# ECU-V1_3.net
KiCad netlist of a schematic drawn in EAGLE
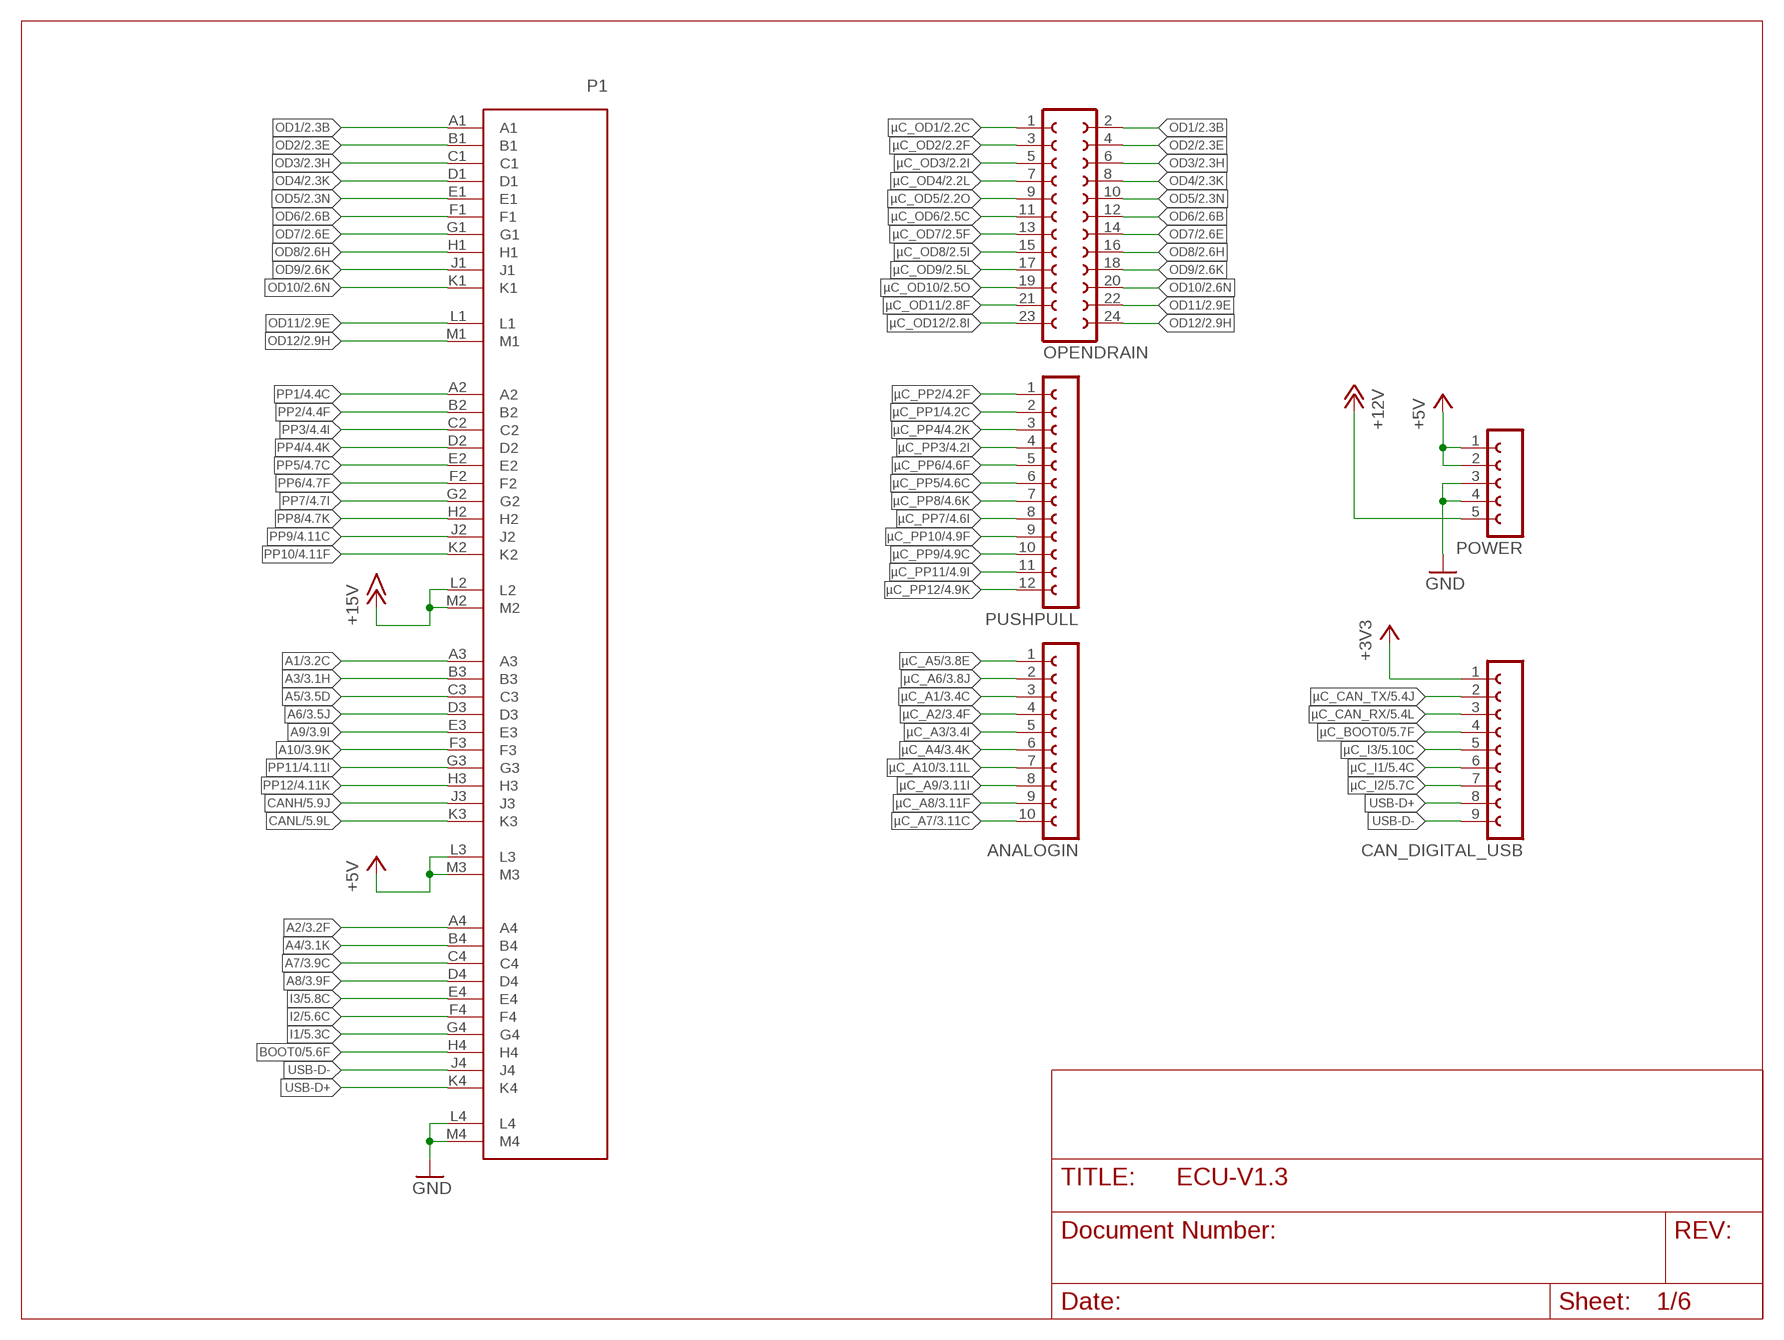
[diagram p0: schematic, sheet 1]
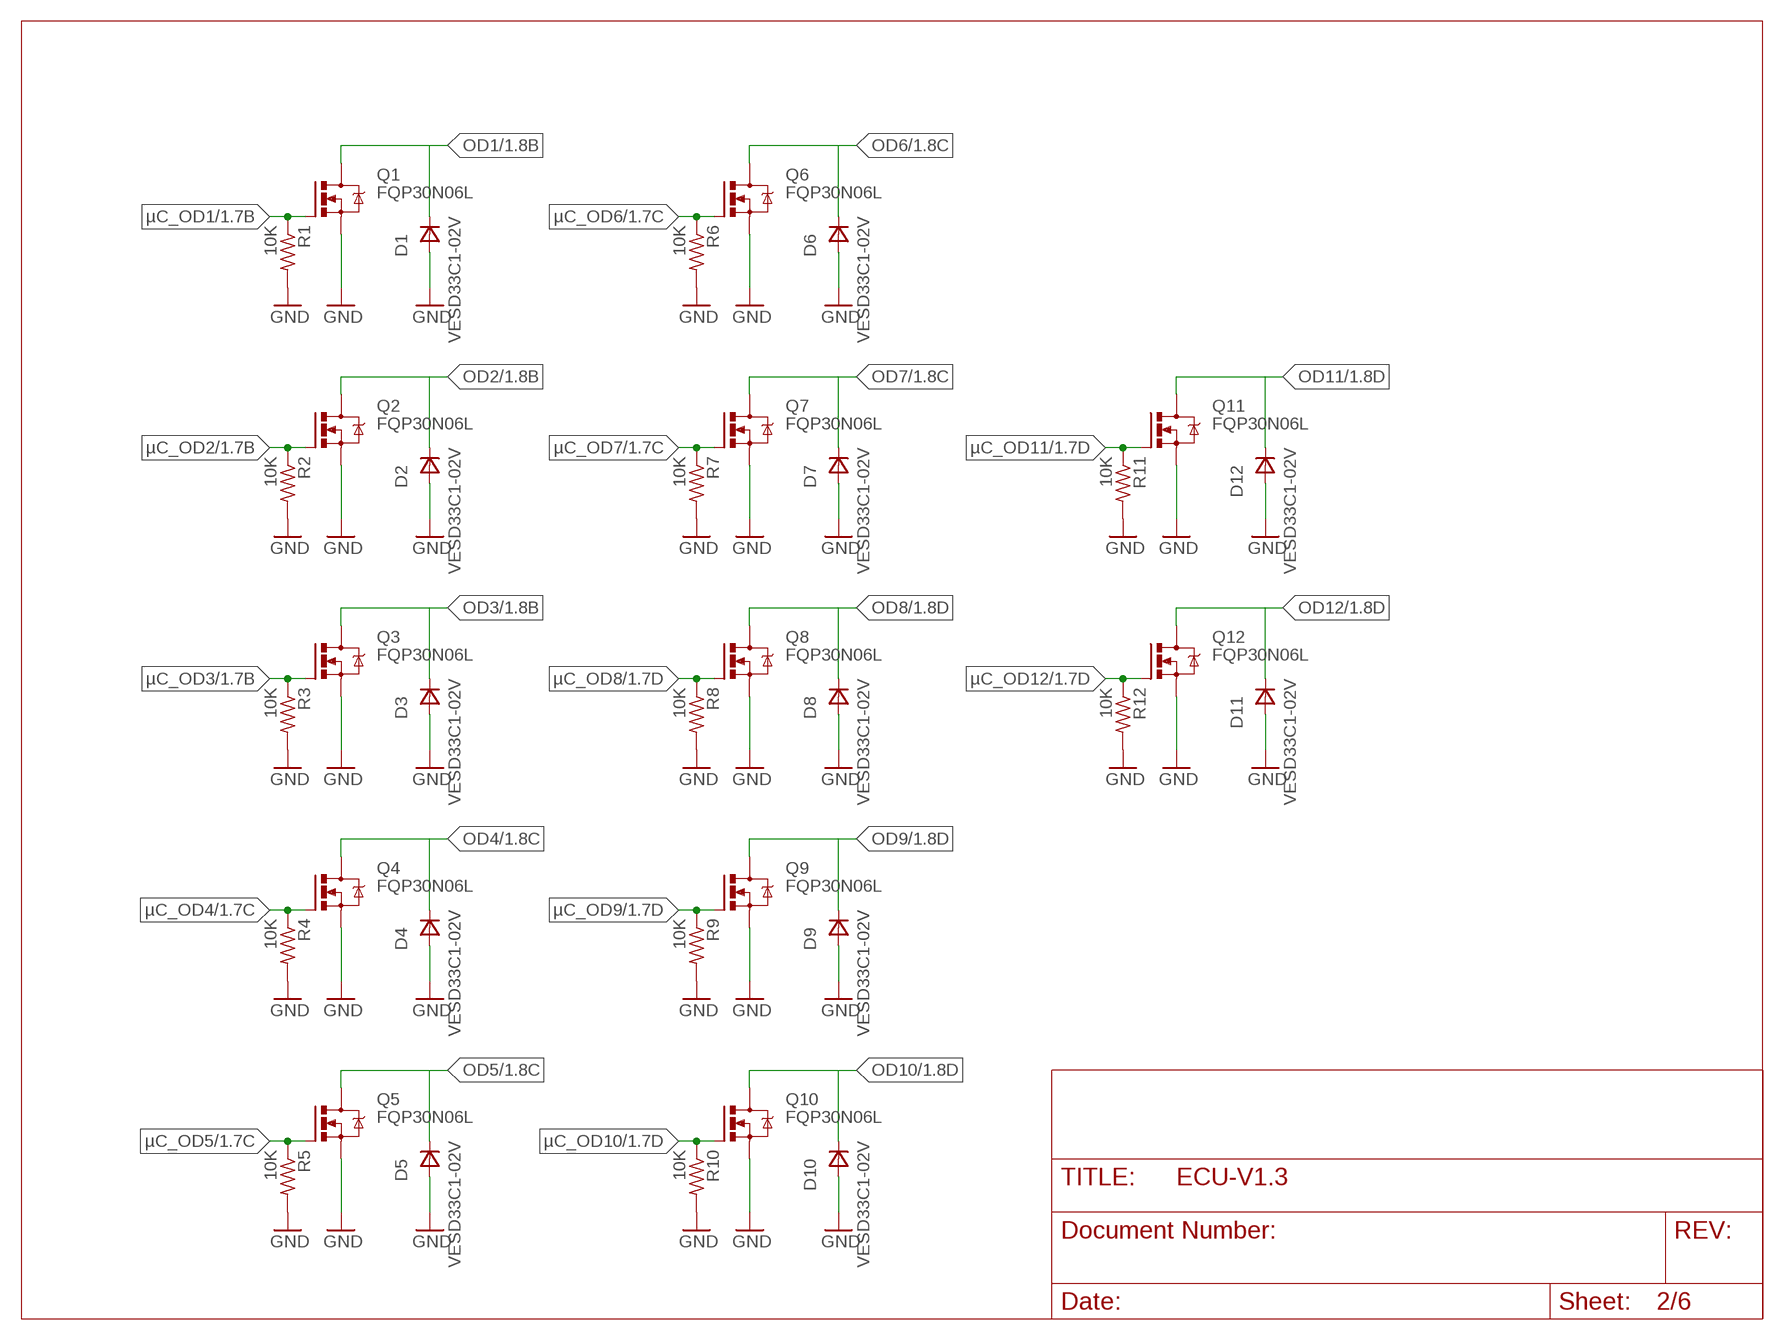
[diagram p1: schematic, sheet 2]
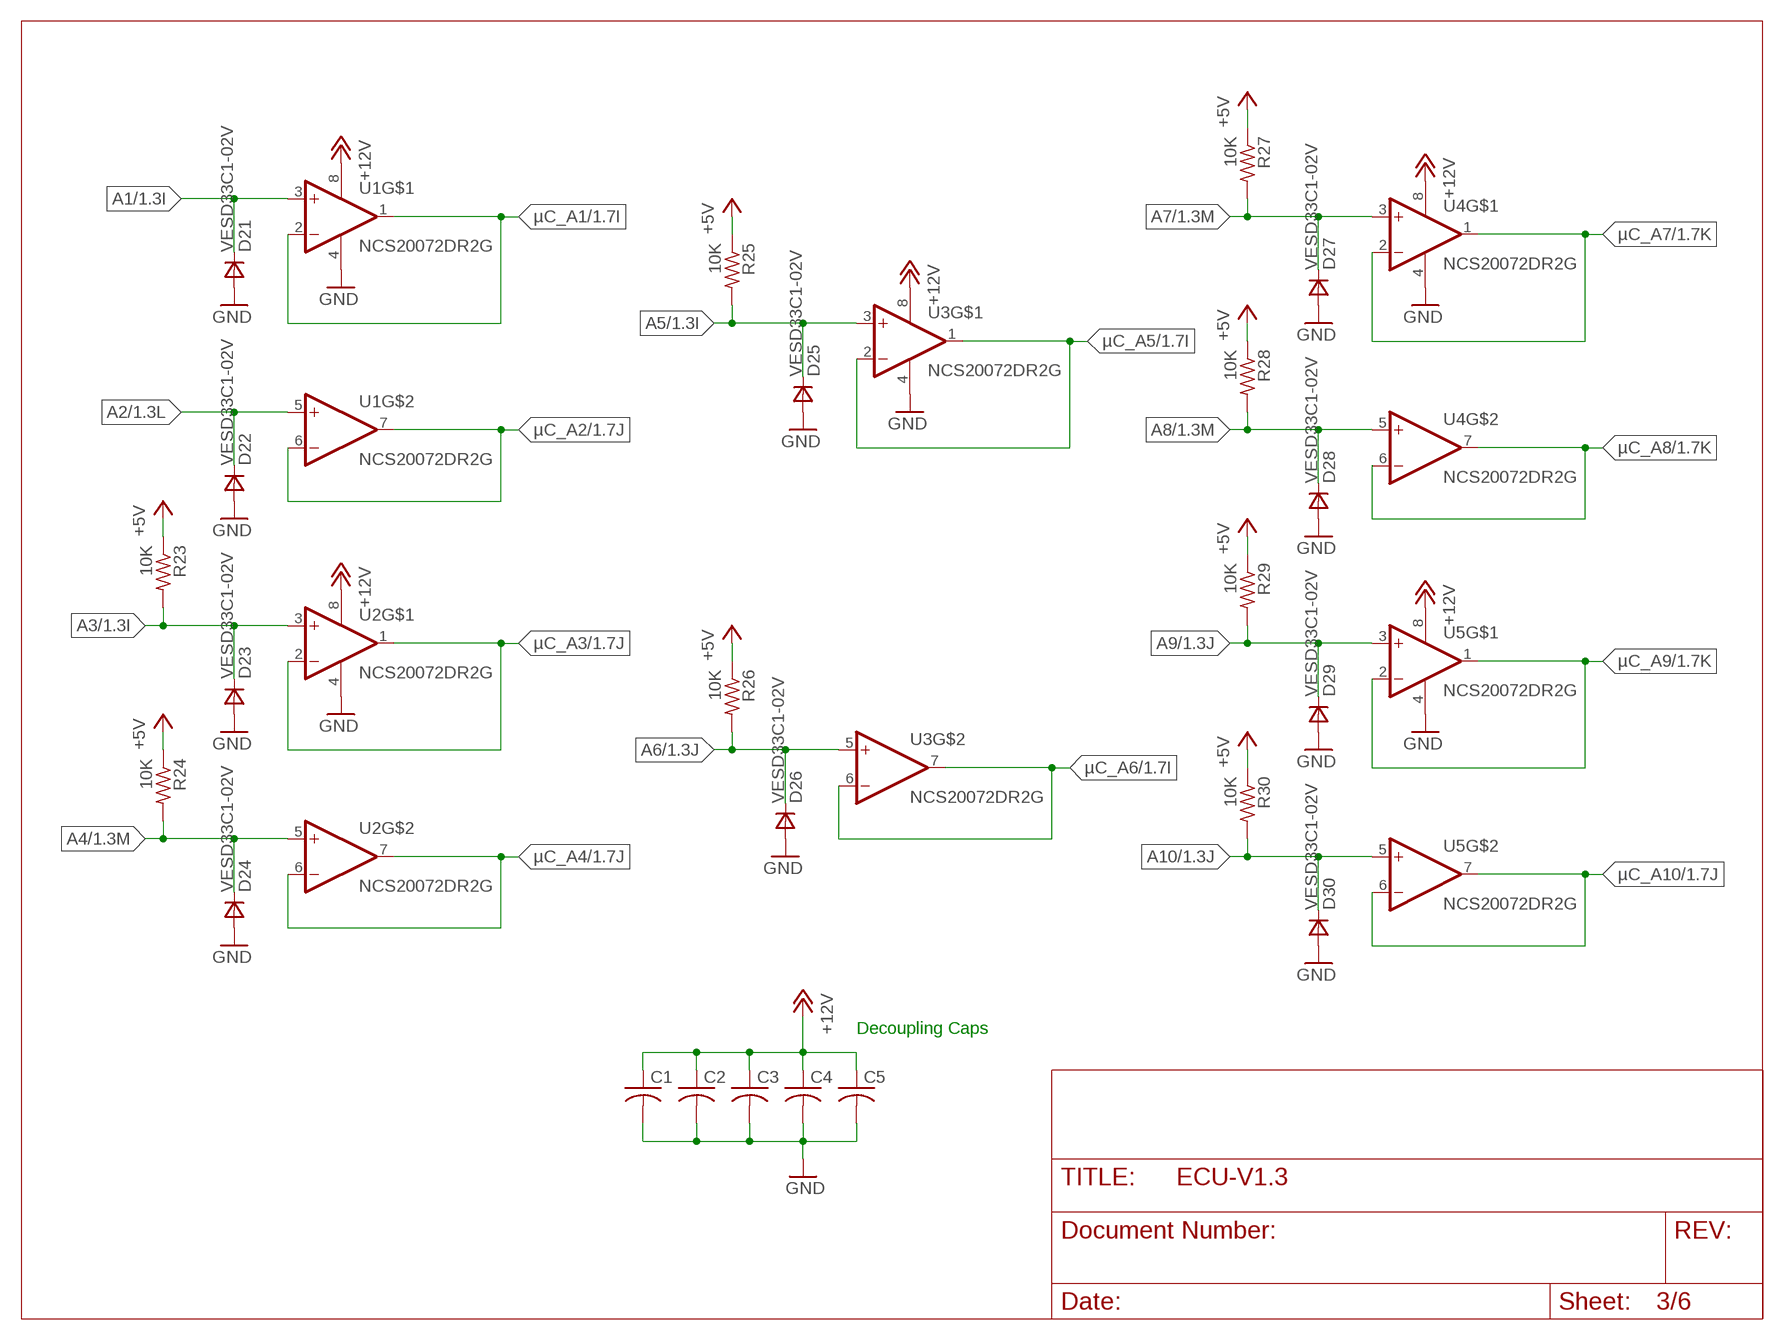
[diagram p2: schematic, sheet 3]
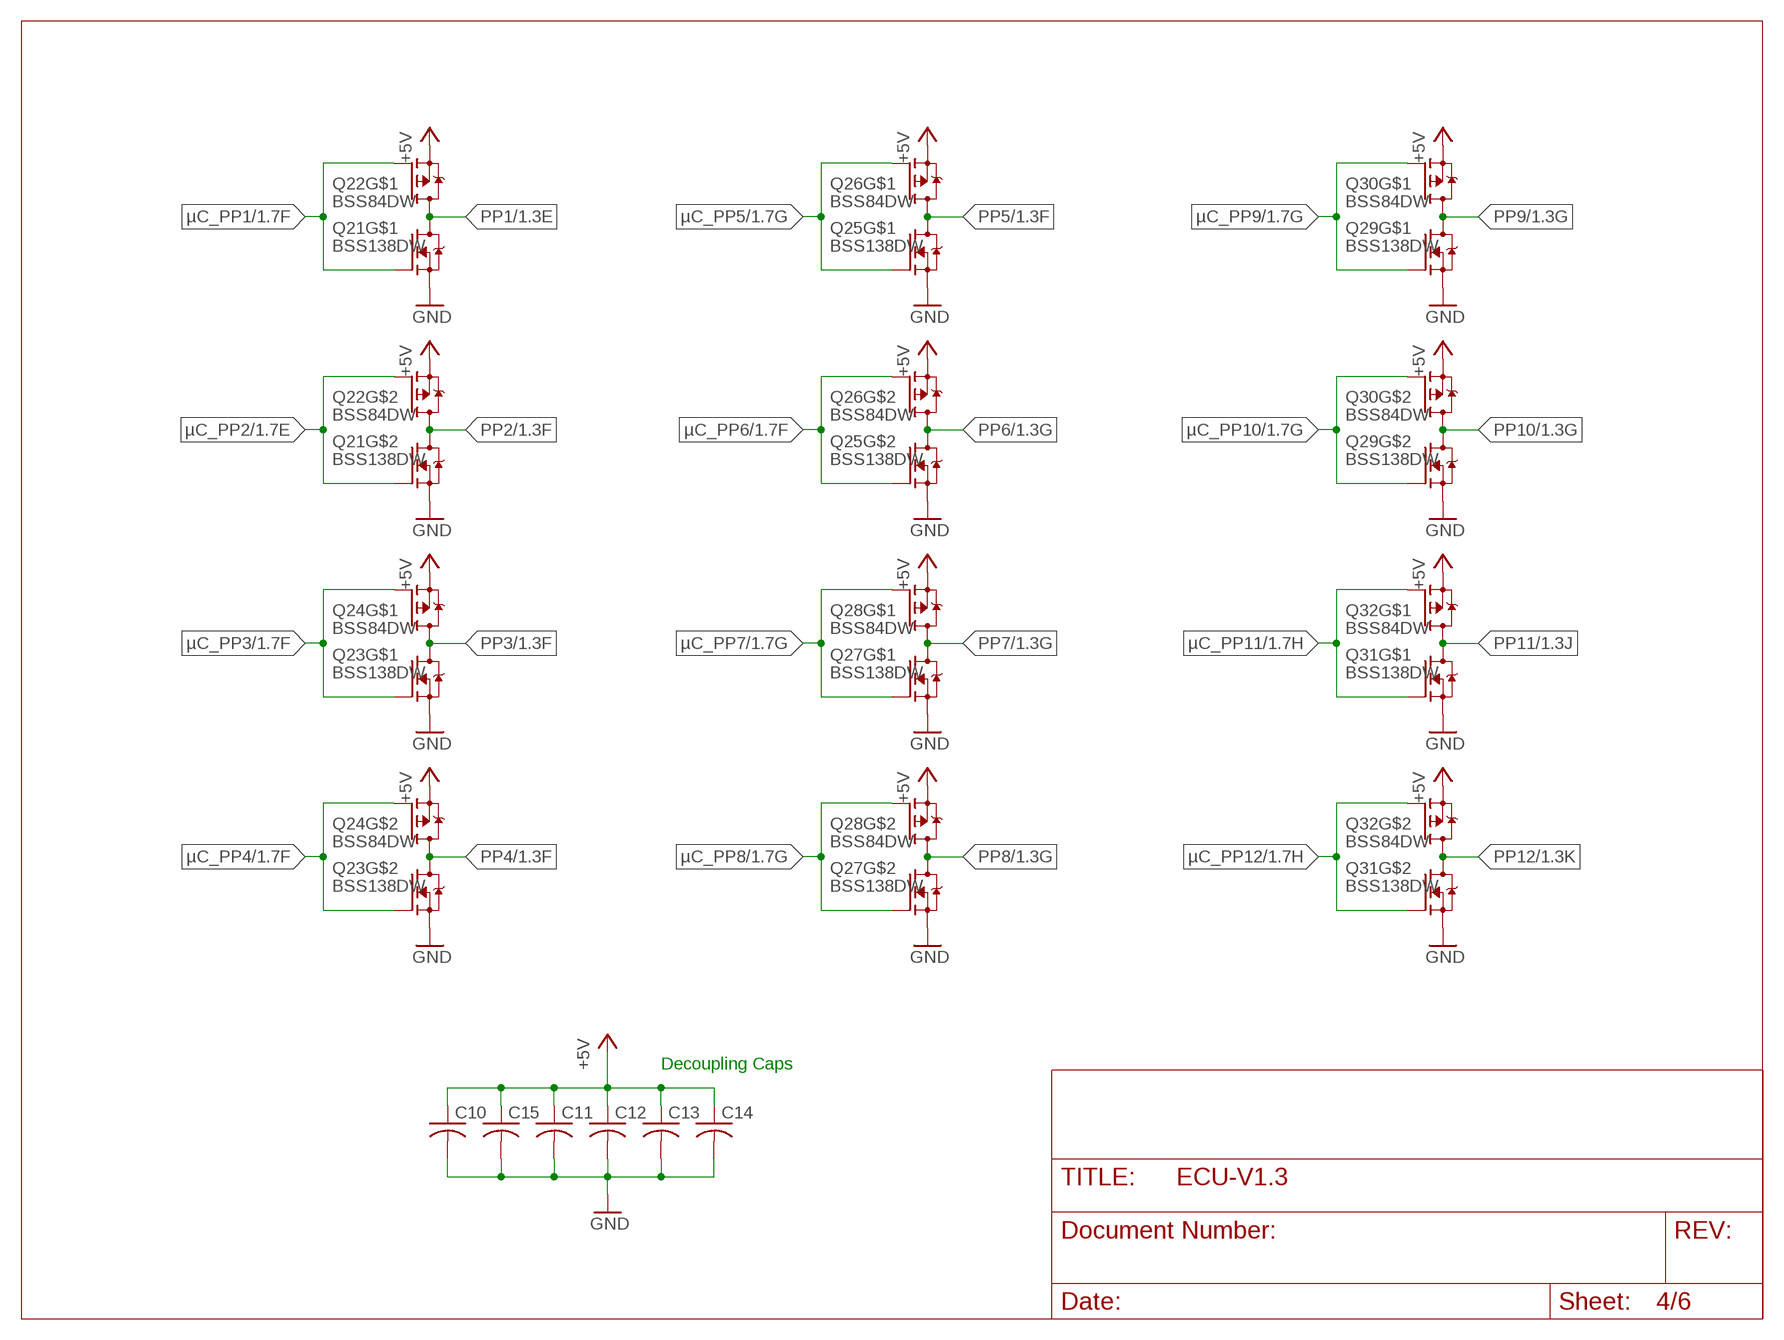
[diagram p3: schematic, sheet 4]
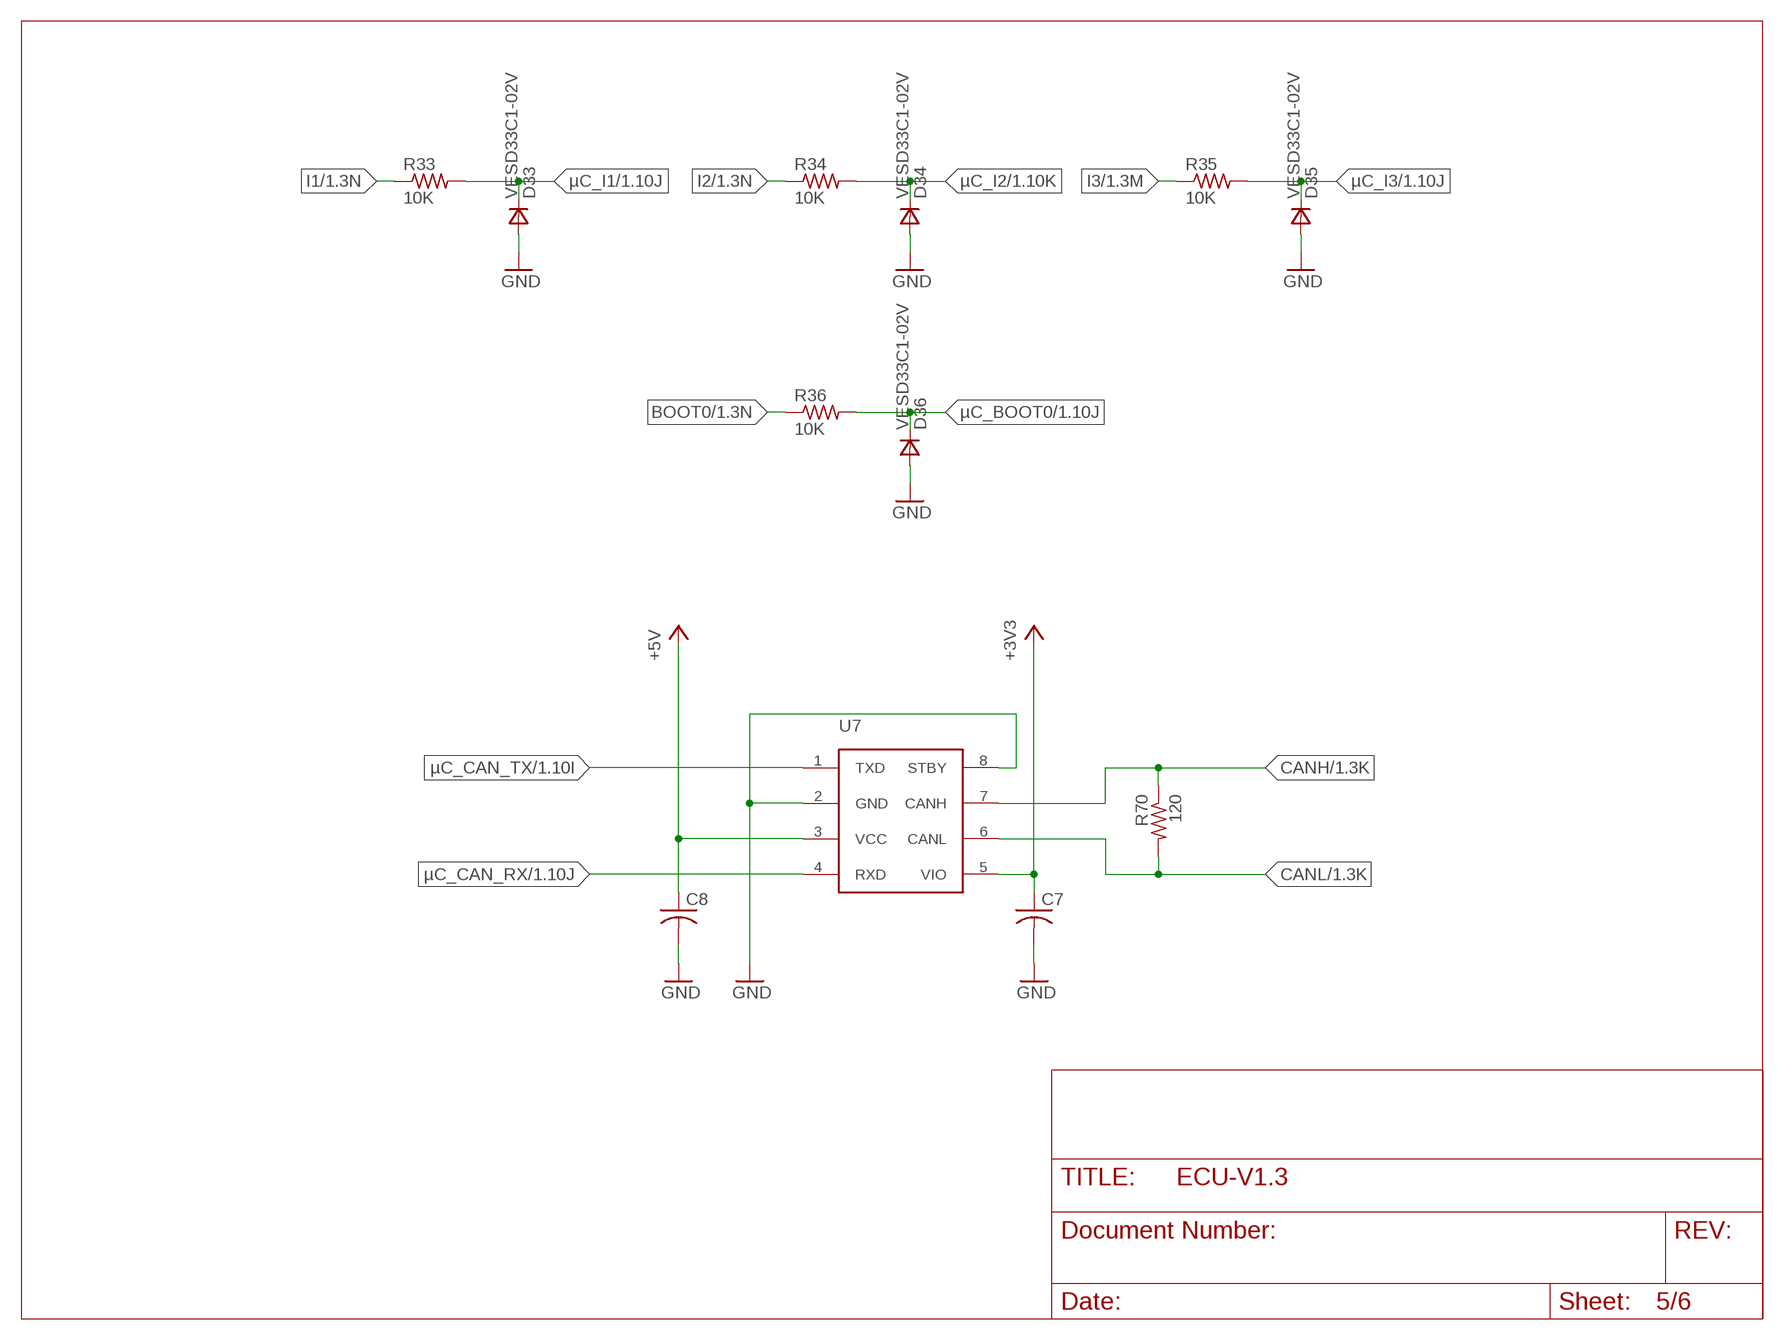
[diagram p4: schematic, sheet 5]
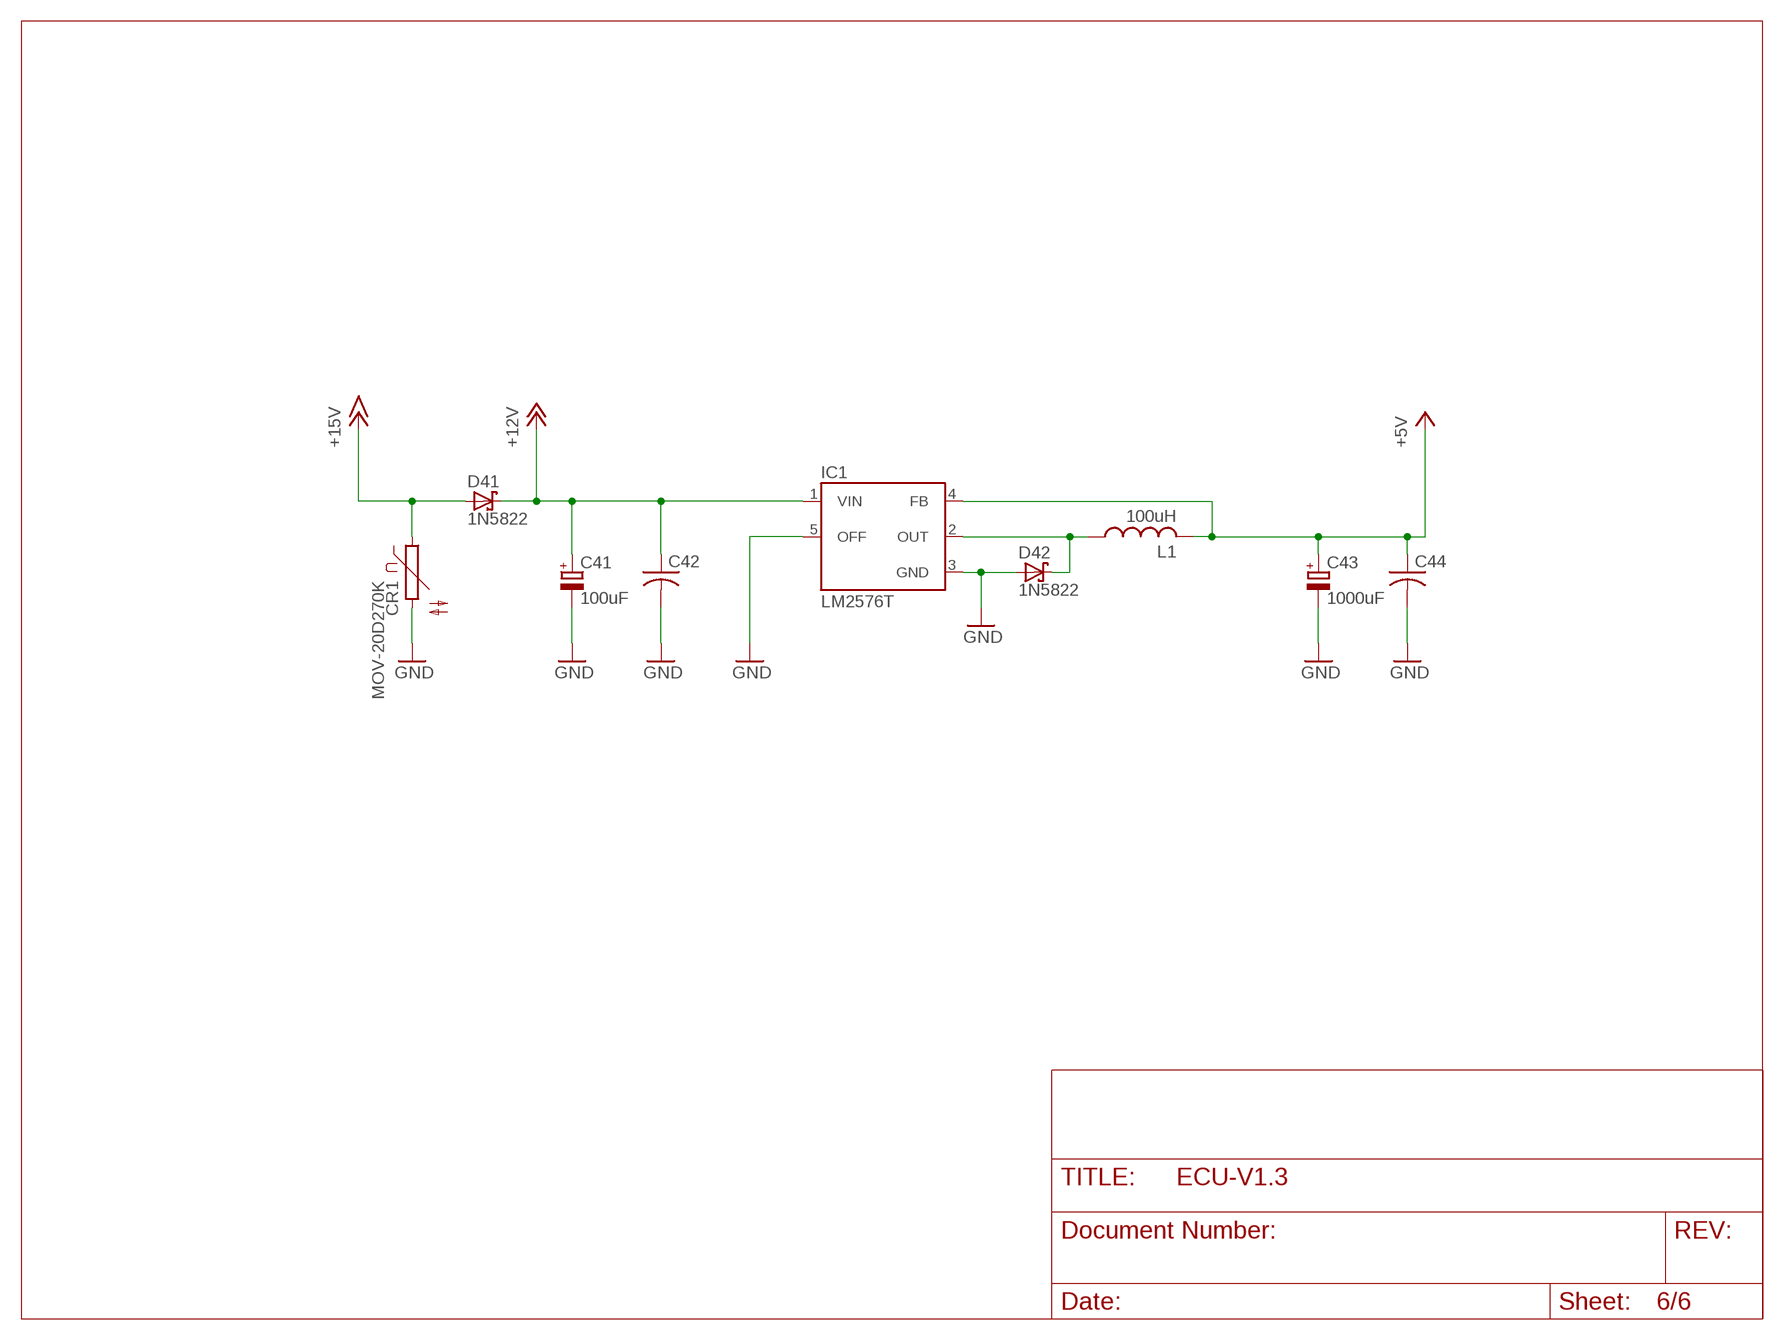
[diagram p5: schematic, sheet 6]

(export (version "E")
  (design (tool "Eeschema 10.0.6"))
  (components
    (comp (ref "C41")
      (value "100uF")
      (footprint "eagle-import:E3,5-10")
      (libsource (lib "eagle-import") (part "CPOL-EUE3.5-10"))
    )
    (comp (ref "C42")
      (value "C-USC0805")
      (footprint "eagle-import:C0805")
      (libsource (lib "eagle-import") (part "C-USC0805"))
    )
    (comp (ref "C43")
      (value "1000uF")
      (footprint "eagle-import:E3,5-10")
      (libsource (lib "eagle-import") (part "CPOL-EUE3.5-10"))
    )
    (comp (ref "C44")
      (value "C-USC0805")
      (footprint "eagle-import:C0805")
      (libsource (lib "eagle-import") (part "C-USC0805"))
    )
    (comp (ref "CR1")
      (value "MOV-20D270K")
      (footprint "eagle-import:S14K40")
      (libsource (lib "eagle-import") (part "S14K40"))
    )
    (comp (ref "D41")
      (value "1N5822")
      (footprint "eagle-import:DIODE_DO35-7")
      (libsource (lib "eagle-import") (part "SCHOTTKY-DIODEDO35-7"))
    )
    (comp (ref "D42")
      (value "1N5822")
      (footprint "eagle-import:DIODE_DO35-7")
      (libsource (lib "eagle-import") (part "SCHOTTKY-DIODEDO35-7"))
    )
    (comp (ref "IC1")
      (value "LM2576T")
      (footprint "eagle-import:TO220-5")
      (libsource (lib "eagle-import") (part "LM2576T"))
    )
    (comp (ref "L1")
      (value "100uH")
      (footprint "eagle-import:6000-XXXX-RC")
      (libsource (lib "eagle-import") (part "L-US6000-XXX-RC"))
    )
    (comp (ref "C1")
      (value "C-USC0805")
      (footprint "eagle-import:C0805")
      (libsource (lib "eagle-import") (part "C-USC0805"))
    )
    (comp (ref "C2")
      (value "C-USC0805")
      (footprint "eagle-import:C0805")
      (libsource (lib "eagle-import") (part "C-USC0805"))
    )
    (comp (ref "C3")
      (value "C-USC0805")
      (footprint "eagle-import:C0805")
      (libsource (lib "eagle-import") (part "C-USC0805"))
    )
    (comp (ref "C4")
      (value "C-USC0805")
      (footprint "eagle-import:C0805")
      (libsource (lib "eagle-import") (part "C-USC0805"))
    )
    (comp (ref "C5")
      (value "C-USC0805")
      (footprint "eagle-import:C0805")
      (libsource (lib "eagle-import") (part "C-USC0805"))
    )
    (comp (ref "D21")
      (value "VESD33C1-02V")
      (footprint "eagle-import:SOD323")
      (fields (field (name "MPN") "CDSOD323-T05C"))
      (libsource (lib "eagle-import") (part "DSOD323"))
    )
    (comp (ref "D22")
      (value "VESD33C1-02V")
      (footprint "eagle-import:SOD323")
      (fields (field (name "MPN") "CDSOD323-T05C"))
      (libsource (lib "eagle-import") (part "DSOD323"))
    )
    (comp (ref "D23")
      (value "VESD33C1-02V")
      (footprint "eagle-import:SOD323")
      (fields (field (name "MPN") "CDSOD323-T05C"))
      (libsource (lib "eagle-import") (part "DSOD323"))
    )
    (comp (ref "D24")
      (value "VESD33C1-02V")
      (footprint "eagle-import:SOD323")
      (fields (field (name "MPN") "CDSOD323-T05C"))
      (libsource (lib "eagle-import") (part "DSOD323"))
    )
    (comp (ref "D25")
      (value "VESD33C1-02V")
      (footprint "eagle-import:SOD323")
      (fields (field (name "MPN") "CDSOD323-T05C"))
      (libsource (lib "eagle-import") (part "DSOD323"))
    )
    (comp (ref "D26")
      (value "VESD33C1-02V")
      (footprint "eagle-import:SOD323")
      (fields (field (name "MPN") "CDSOD323-T05C"))
      (libsource (lib "eagle-import") (part "DSOD323"))
    )
    (comp (ref "D27")
      (value "VESD33C1-02V")
      (footprint "eagle-import:SOD323")
      (fields (field (name "MPN") "CDSOD323-T05C"))
      (libsource (lib "eagle-import") (part "DSOD323"))
    )
    (comp (ref "D28")
      (value "VESD33C1-02V")
      (footprint "eagle-import:SOD323")
      (fields (field (name "MPN") "CDSOD323-T05C"))
      (libsource (lib "eagle-import") (part "DSOD323"))
    )
    (comp (ref "D29")
      (value "VESD33C1-02V")
      (footprint "eagle-import:SOD323")
      (fields (field (name "MPN") "CDSOD323-T05C"))
      (libsource (lib "eagle-import") (part "DSOD323"))
    )
    (comp (ref "D30")
      (value "VESD33C1-02V")
      (footprint "eagle-import:SOD323")
      (fields (field (name "MPN") "CDSOD323-T05C"))
      (libsource (lib "eagle-import") (part "DSOD323"))
    )
    (comp (ref "R23")
      (value "10K")
      (footprint "eagle-import:R0805")
      (libsource (lib "eagle-import") (part "R-US_R0805"))
    )
    (comp (ref "R24")
      (value "10K")
      (footprint "eagle-import:R0805")
      (libsource (lib "eagle-import") (part "R-US_R0805"))
    )
    (comp (ref "R25")
      (value "10K")
      (footprint "eagle-import:R0805")
      (libsource (lib "eagle-import") (part "R-US_R0805"))
    )
    (comp (ref "R26")
      (value "10K")
      (footprint "eagle-import:R0805")
      (libsource (lib "eagle-import") (part "R-US_R0805"))
    )
    (comp (ref "R27")
      (value "10K")
      (footprint "eagle-import:R0805")
      (libsource (lib "eagle-import") (part "R-US_R0805"))
    )
    (comp (ref "R28")
      (value "10K")
      (footprint "eagle-import:R0805")
      (libsource (lib "eagle-import") (part "R-US_R0805"))
    )
    (comp (ref "R29")
      (value "10K")
      (footprint "eagle-import:R0805")
      (libsource (lib "eagle-import") (part "R-US_R0805"))
    )
    (comp (ref "R30")
      (value "10K")
      (footprint "eagle-import:R0805")
      (libsource (lib "eagle-import") (part "R-US_R0805"))
    )
    (comp (ref "U1")
      (value "NCS20072DR2G")
      (footprint "eagle-import:SOIC8")
      (libsource (lib "eagle-import") (part "NCS20072DR2G"))
    )
    (comp (ref "U2")
      (value "NCS20072DR2G")
      (footprint "eagle-import:SOIC8")
      (libsource (lib "eagle-import") (part "NCS20072DR2G"))
    )
    (comp (ref "U3")
      (value "NCS20072DR2G")
      (footprint "eagle-import:SOIC8")
      (libsource (lib "eagle-import") (part "NCS20072DR2G"))
    )
    (comp (ref "U4")
      (value "NCS20072DR2G")
      (footprint "eagle-import:SOIC8")
      (libsource (lib "eagle-import") (part "NCS20072DR2G"))
    )
    (comp (ref "U5")
      (value "NCS20072DR2G")
      (footprint "eagle-import:SOIC8")
      (libsource (lib "eagle-import") (part "NCS20072DR2G"))
    )
    (comp (ref "D1")
      (value "VESD33C1-02V")
      (footprint "eagle-import:SOD323")
      (fields (field (name "MPN") "CDSOD323-T05C"))
      (libsource (lib "eagle-import") (part "DSOD323"))
    )
    (comp (ref "D2")
      (value "VESD33C1-02V")
      (footprint "eagle-import:SOD323")
      (fields (field (name "MPN") "CDSOD323-T05C"))
      (libsource (lib "eagle-import") (part "DSOD323"))
    )
    (comp (ref "D3")
      (value "VESD33C1-02V")
      (footprint "eagle-import:SOD323")
      (fields (field (name "MPN") "CDSOD323-T05C"))
      (libsource (lib "eagle-import") (part "DSOD323"))
    )
    (comp (ref "D4")
      (value "VESD33C1-02V")
      (footprint "eagle-import:SOD323")
      (fields (field (name "MPN") "CDSOD323-T05C"))
      (libsource (lib "eagle-import") (part "DSOD323"))
    )
    (comp (ref "D5")
      (value "VESD33C1-02V")
      (footprint "eagle-import:SOD323")
      (fields (field (name "MPN") "CDSOD323-T05C"))
      (libsource (lib "eagle-import") (part "DSOD323"))
    )
    (comp (ref "D6")
      (value "VESD33C1-02V")
      (footprint "eagle-import:SOD323")
      (fields (field (name "MPN") "CDSOD323-T05C"))
      (libsource (lib "eagle-import") (part "DSOD323"))
    )
    (comp (ref "D7")
      (value "VESD33C1-02V")
      (footprint "eagle-import:SOD323")
      (fields (field (name "MPN") "CDSOD323-T05C"))
      (libsource (lib "eagle-import") (part "DSOD323"))
    )
    (comp (ref "D8")
      (value "VESD33C1-02V")
      (footprint "eagle-import:SOD323")
      (fields (field (name "MPN") "CDSOD323-T05C"))
      (libsource (lib "eagle-import") (part "DSOD323"))
    )
    (comp (ref "D9")
      (value "VESD33C1-02V")
      (footprint "eagle-import:SOD323")
      (fields (field (name "MPN") "CDSOD323-T05C"))
      (libsource (lib "eagle-import") (part "DSOD323"))
    )
    (comp (ref "D10")
      (value "VESD33C1-02V")
      (footprint "eagle-import:SOD323")
      (fields (field (name "MPN") "CDSOD323-T05C"))
      (libsource (lib "eagle-import") (part "DSOD323"))
    )
    (comp (ref "D11")
      (value "VESD33C1-02V")
      (footprint "eagle-import:SOD323")
      (fields (field (name "MPN") "CDSOD323-T05C"))
      (libsource (lib "eagle-import") (part "DSOD323"))
    )
    (comp (ref "D12")
      (value "VESD33C1-02V")
      (footprint "eagle-import:SOD323")
      (fields (field (name "MPN") "CDSOD323-T05C"))
      (libsource (lib "eagle-import") (part "DSOD323"))
    )
    (comp (ref "Q1")
      (value "FQP30N06L")
      (footprint "eagle-import:TO220BV")
      (libsource (lib "eagle-import") (part "FQP30N06L"))
    )
    (comp (ref "Q2")
      (value "FQP30N06L")
      (footprint "eagle-import:TO220BV")
      (libsource (lib "eagle-import") (part "FQP30N06L"))
    )
    (comp (ref "Q3")
      (value "FQP30N06L")
      (footprint "eagle-import:TO220BV")
      (libsource (lib "eagle-import") (part "FQP30N06L"))
    )
    (comp (ref "Q4")
      (value "FQP30N06L")
      (footprint "eagle-import:TO220BV")
      (libsource (lib "eagle-import") (part "FQP30N06L"))
    )
    (comp (ref "Q5")
      (value "FQP30N06L")
      (footprint "eagle-import:TO220BV")
      (libsource (lib "eagle-import") (part "FQP30N06L"))
    )
    (comp (ref "Q6")
      (value "FQP30N06L")
      (footprint "eagle-import:TO220BV")
      (libsource (lib "eagle-import") (part "FQP30N06L"))
    )
    (comp (ref "Q7")
      (value "FQP30N06L")
      (footprint "eagle-import:TO220BV")
      (libsource (lib "eagle-import") (part "FQP30N06L"))
    )
    (comp (ref "Q8")
      (value "FQP30N06L")
      (footprint "eagle-import:TO220BV")
      (libsource (lib "eagle-import") (part "FQP30N06L"))
    )
    (comp (ref "Q9")
      (value "FQP30N06L")
      (footprint "eagle-import:TO220BV")
      (libsource (lib "eagle-import") (part "FQP30N06L"))
    )
    (comp (ref "Q10")
      (value "FQP30N06L")
      (footprint "eagle-import:TO220BV")
      (libsource (lib "eagle-import") (part "FQP30N06L"))
    )
    (comp (ref "Q11")
      (value "FQP30N06L")
      (footprint "eagle-import:TO220BV")
      (libsource (lib "eagle-import") (part "FQP30N06L"))
    )
    (comp (ref "Q12")
      (value "FQP30N06L")
      (footprint "eagle-import:TO220BV")
      (libsource (lib "eagle-import") (part "FQP30N06L"))
    )
    (comp (ref "R1")
      (value "10K")
      (footprint "eagle-import:R0805")
      (libsource (lib "eagle-import") (part "R-US_R0805"))
    )
    (comp (ref "R2")
      (value "10K")
      (footprint "eagle-import:R0805")
      (libsource (lib "eagle-import") (part "R-US_R0805"))
    )
    (comp (ref "R3")
      (value "10K")
      (footprint "eagle-import:R0805")
      (libsource (lib "eagle-import") (part "R-US_R0805"))
    )
    (comp (ref "R4")
      (value "10K")
      (footprint "eagle-import:R0805")
      (libsource (lib "eagle-import") (part "R-US_R0805"))
    )
    (comp (ref "R5")
      (value "10K")
      (footprint "eagle-import:R0805")
      (libsource (lib "eagle-import") (part "R-US_R0805"))
    )
    (comp (ref "R6")
      (value "10K")
      (footprint "eagle-import:R0805")
      (libsource (lib "eagle-import") (part "R-US_R0805"))
    )
    (comp (ref "R7")
      (value "10K")
      (footprint "eagle-import:R0805")
      (libsource (lib "eagle-import") (part "R-US_R0805"))
    )
    (comp (ref "R8")
      (value "10K")
      (footprint "eagle-import:R0805")
      (libsource (lib "eagle-import") (part "R-US_R0805"))
    )
    (comp (ref "R9")
      (value "10K")
      (footprint "eagle-import:R0805")
      (libsource (lib "eagle-import") (part "R-US_R0805"))
    )
    (comp (ref "R10")
      (value "10K")
      (footprint "eagle-import:R0805")
      (libsource (lib "eagle-import") (part "R-US_R0805"))
    )
    (comp (ref "R11")
      (value "10K")
      (footprint "eagle-import:R0805")
      (libsource (lib "eagle-import") (part "R-US_R0805"))
    )
    (comp (ref "R12")
      (value "10K")
      (footprint "eagle-import:R0805")
      (libsource (lib "eagle-import") (part "R-US_R0805"))
    )
    (comp (ref "ANALOGIN")
      (value "FE10-1")
      (footprint "eagle-import:FE10")
      (libsource (lib "eagle-import") (part "FE10-1"))
    )
    (comp (ref "CAN_DIGITAL_USB")
      (value "FE09-1")
      (footprint "eagle-import:FE09")
      (libsource (lib "eagle-import") (part "FE09-1"))
    )
    (comp (ref "OPENDRAIN")
      (value "FE12-2")
      (footprint "eagle-import:FE12-2")
      (libsource (lib "eagle-import") (part "FE12-2"))
    )
    (comp (ref "P1")
      (value "ECU-CONNECTOR")
      (footprint "eagle-import:ECU-CONNECTOR")
      (libsource (lib "eagle-import") (part "ECU-CONNECTOR"))
    )
    (comp (ref "POWER")
      (value "FE05-1")
      (footprint "eagle-import:FE05-1")
      (libsource (lib "eagle-import") (part "FE05-1"))
    )
    (comp (ref "PUSHPULL")
      (value "FE12-1")
      (footprint "eagle-import:FE12")
      (libsource (lib "eagle-import") (part "FE12-1"))
    )
    (comp (ref "C10")
      (value "C-USC0805")
      (footprint "eagle-import:C0805")
      (libsource (lib "eagle-import") (part "C-USC0805"))
    )
    (comp (ref "C11")
      (value "C-USC0805")
      (footprint "eagle-import:C0805")
      (libsource (lib "eagle-import") (part "C-USC0805"))
    )
    (comp (ref "C12")
      (value "C-USC0805")
      (footprint "eagle-import:C0805")
      (libsource (lib "eagle-import") (part "C-USC0805"))
    )
    (comp (ref "C13")
      (value "C-USC0805")
      (footprint "eagle-import:C0805")
      (libsource (lib "eagle-import") (part "C-USC0805"))
    )
    (comp (ref "C14")
      (value "C-USC0805")
      (footprint "eagle-import:C0805")
      (libsource (lib "eagle-import") (part "C-USC0805"))
    )
    (comp (ref "C15")
      (value "C-USC0805")
      (footprint "eagle-import:C0805")
      (libsource (lib "eagle-import") (part "C-USC0805"))
    )
    (comp (ref "Q21")
      (value "BSS138DW")
      (footprint "eagle-import:SOT363_INFINEON")
      (libsource (lib "eagle-import") (part "BSS138DW"))
    )
    (comp (ref "Q22")
      (value "BSS84DW")
      (footprint "eagle-import:SOT363_INFINEON")
      (libsource (lib "eagle-import") (part "BSS84DW"))
    )
    (comp (ref "Q23")
      (value "BSS138DW")
      (footprint "eagle-import:SOT363_INFINEON")
      (libsource (lib "eagle-import") (part "BSS138DW"))
    )
    (comp (ref "Q24")
      (value "BSS84DW")
      (footprint "eagle-import:SOT363_INFINEON")
      (libsource (lib "eagle-import") (part "BSS84DW"))
    )
    (comp (ref "Q25")
      (value "BSS138DW")
      (footprint "eagle-import:SOT363_INFINEON")
      (libsource (lib "eagle-import") (part "BSS138DW"))
    )
    (comp (ref "Q26")
      (value "BSS84DW")
      (footprint "eagle-import:SOT363_INFINEON")
      (libsource (lib "eagle-import") (part "BSS84DW"))
    )
    (comp (ref "Q27")
      (value "BSS138DW")
      (footprint "eagle-import:SOT363_INFINEON")
      (libsource (lib "eagle-import") (part "BSS138DW"))
    )
    (comp (ref "Q28")
      (value "BSS84DW")
      (footprint "eagle-import:SOT363_INFINEON")
      (libsource (lib "eagle-import") (part "BSS84DW"))
    )
    (comp (ref "Q29")
      (value "BSS138DW")
      (footprint "eagle-import:SOT363_INFINEON")
      (libsource (lib "eagle-import") (part "BSS138DW"))
    )
    (comp (ref "Q30")
      (value "BSS84DW")
      (footprint "eagle-import:SOT363_INFINEON")
      (libsource (lib "eagle-import") (part "BSS84DW"))
    )
    (comp (ref "Q31")
      (value "BSS138DW")
      (footprint "eagle-import:SOT363_INFINEON")
      (libsource (lib "eagle-import") (part "BSS138DW"))
    )
    (comp (ref "Q32")
      (value "BSS84DW")
      (footprint "eagle-import:SOT363_INFINEON")
      (libsource (lib "eagle-import") (part "BSS84DW"))
    )
    (comp (ref "C7")
      (value "C-USC0805")
      (footprint "eagle-import:C0805")
      (libsource (lib "eagle-import") (part "C-USC0805"))
    )
    (comp (ref "C8")
      (value "C-USC0805")
      (footprint "eagle-import:C0805")
      (libsource (lib "eagle-import") (part "C-USC0805"))
    )
    (comp (ref "D33")
      (value "VESD33C1-02V")
      (footprint "eagle-import:SOD323")
      (fields (field (name "MPN") "CDSOD323-T05C"))
      (libsource (lib "eagle-import") (part "DSOD323"))
    )
    (comp (ref "D34")
      (value "VESD33C1-02V")
      (footprint "eagle-import:SOD323")
      (fields (field (name "MPN") "CDSOD323-T05C"))
      (libsource (lib "eagle-import") (part "DSOD323"))
    )
    (comp (ref "D35")
      (value "VESD33C1-02V")
      (footprint "eagle-import:SOD323")
      (fields (field (name "MPN") "CDSOD323-T05C"))
      (libsource (lib "eagle-import") (part "DSOD323"))
    )
    (comp (ref "D36")
      (value "VESD33C1-02V")
      (footprint "eagle-import:SOD323")
      (fields (field (name "MPN") "CDSOD323-T05C"))
      (libsource (lib "eagle-import") (part "DSOD323"))
    )
    (comp (ref "R33")
      (value "10K")
      (footprint "eagle-import:R0805")
      (libsource (lib "eagle-import") (part "R-US_R0805"))
    )
    (comp (ref "R34")
      (value "10K")
      (footprint "eagle-import:R0805")
      (libsource (lib "eagle-import") (part "R-US_R0805"))
    )
    (comp (ref "R35")
      (value "10K")
      (footprint "eagle-import:R0805")
      (libsource (lib "eagle-import") (part "R-US_R0805"))
    )
    (comp (ref "R36")
      (value "10K")
      (footprint "eagle-import:R0805")
      (libsource (lib "eagle-import") (part "R-US_R0805"))
    )
    (comp (ref "R70")
      (value "120")
      (footprint "eagle-import:R0805")
      (libsource (lib "eagle-import") (part "R-US_R0805"))
    )
    (comp (ref "U7")
      (value "ATA6561-GA")
      (footprint "eagle-import:SO-08")
      (libsource (lib "eagle-import") (part "ATA6561-GA"))
    )
  )
  (nets
    (net (code "1") (name "+3V3") (class "Default")
      (node (ref "C7") (pin "1") (pinfunction "1_1") (pintype "passive"))
      (node (ref "CAN_DIGITAL_USB") (pin "1") (pinfunction "1_1") (pintype "passive"))
      (node (ref "U7") (pin "5") (pinfunction "VIO_5") (pintype "bidirectional"))
    )
    (net (code "2") (name "+5V") (class "Default")
      (node (ref "C10") (pin "1") (pinfunction "1_1") (pintype "passive"))
      (node (ref "C11") (pin "1") (pinfunction "1_1") (pintype "passive"))
      (node (ref "C12") (pin "1") (pinfunction "1_1") (pintype "passive"))
      (node (ref "C13") (pin "1") (pinfunction "1_1") (pintype "passive"))
      (node (ref "C14") (pin "1") (pinfunction "1_1") (pintype "passive"))
      (node (ref "C15") (pin "1") (pinfunction "1_1") (pintype "passive"))
      (node (ref "C43") (pin "+") (pinfunction "+_+") (pintype "passive"))
      (node (ref "C44") (pin "1") (pinfunction "1_1") (pintype "passive"))
      (node (ref "C8") (pin "1") (pinfunction "1_1") (pintype "passive"))
      (node (ref "IC1") (pin "4") (pinfunction "FB_4") (pintype "input"))
      (node (ref "L1") (pin "2") (pinfunction "2_2") (pintype "passive"))
      (node (ref "P1") (pin "L3") (pinfunction "L3_L3") (pintype "bidirectional"))
      (node (ref "P1") (pin "M3") (pinfunction "M3_M3") (pintype "bidirectional"))
      (node (ref "POWER") (pin "1") (pinfunction "1_1") (pintype "passive"))
      (node (ref "POWER") (pin "2") (pinfunction "2_2") (pintype "passive"))
      (node (ref "Q22") (pin "1") (pinfunction "S_1") (pintype "passive"))
      (node (ref "Q22") (pin "4") (pinfunction "S_4") (pintype "passive"))
      (node (ref "Q24") (pin "1") (pinfunction "S_1") (pintype "passive"))
      (node (ref "Q24") (pin "4") (pinfunction "S_4") (pintype "passive"))
      (node (ref "Q26") (pin "1") (pinfunction "S_1") (pintype "passive"))
      (node (ref "Q26") (pin "4") (pinfunction "S_4") (pintype "passive"))
      (node (ref "Q28") (pin "1") (pinfunction "S_1") (pintype "passive"))
      (node (ref "Q28") (pin "4") (pinfunction "S_4") (pintype "passive"))
      (node (ref "Q30") (pin "1") (pinfunction "S_1") (pintype "passive"))
      (node (ref "Q30") (pin "4") (pinfunction "S_4") (pintype "passive"))
      (node (ref "Q32") (pin "1") (pinfunction "S_1") (pintype "passive"))
      (node (ref "Q32") (pin "4") (pinfunction "S_4") (pintype "passive"))
      (node (ref "R23") (pin "1") (pinfunction "1_1") (pintype "passive"))
      (node (ref "R24") (pin "1") (pinfunction "1_1") (pintype "passive"))
      (node (ref "R25") (pin "1") (pinfunction "1_1") (pintype "passive"))
      (node (ref "R26") (pin "1") (pinfunction "1_1") (pintype "passive"))
      (node (ref "R27") (pin "1") (pinfunction "1_1") (pintype "passive"))
      (node (ref "R28") (pin "1") (pinfunction "1_1") (pintype "passive"))
      (node (ref "R29") (pin "1") (pinfunction "1_1") (pintype "passive"))
      (node (ref "R30") (pin "1") (pinfunction "1_1") (pintype "passive"))
      (node (ref "U7") (pin "3") (pinfunction "VCC_3") (pintype "bidirectional"))
    )
    (net (code "3") (name "+12V") (class "Default")
      (node (ref "C1") (pin "1") (pinfunction "1_1") (pintype "passive"))
      (node (ref "C2") (pin "1") (pinfunction "1_1") (pintype "passive"))
      (node (ref "C3") (pin "1") (pinfunction "1_1") (pintype "passive"))
      (node (ref "C4") (pin "1") (pinfunction "1_1") (pintype "passive"))
      (node (ref "C41") (pin "+") (pinfunction "+_+") (pintype "passive"))
      (node (ref "C42") (pin "1") (pinfunction "1_1") (pintype "passive"))
      (node (ref "C5") (pin "1") (pinfunction "1_1") (pintype "passive"))
      (node (ref "D41") (pin "C") (pinfunction "A_C") (pintype "passive"))
      (node (ref "IC1") (pin "1") (pinfunction "VIN_1") (pintype "power_in"))
      (node (ref "POWER") (pin "5") (pinfunction "5_5") (pintype "passive"))
      (node (ref "U1") (pin "8") (pinfunction "V+_8") (pintype "power_in"))
      (node (ref "U2") (pin "8") (pinfunction "V+_8") (pintype "power_in"))
      (node (ref "U3") (pin "8") (pinfunction "V+_8") (pintype "power_in"))
      (node (ref "U4") (pin "8") (pinfunction "V+_8") (pintype "power_in"))
      (node (ref "U5") (pin "8") (pinfunction "V+_8") (pintype "power_in"))
    )
    (net (code "4") (name "+15V") (class "Default")
      (node (ref "CR1") (pin "1") (pinfunction "1_1") (pintype "passive"))
      (node (ref "D41") (pin "A") (pinfunction "C_A") (pintype "passive"))
      (node (ref "P1") (pin "L2") (pinfunction "L2_L2") (pintype "bidirectional"))
      (node (ref "P1") (pin "M2") (pinfunction "M2_M2") (pintype "bidirectional"))
    )
    (net (code "5") (name "A1") (class "Default")
      (node (ref "D21") (pin "1") (pinfunction "C_1") (pintype "passive"))
      (node (ref "P1") (pin "A3") (pinfunction "A3_A3") (pintype "bidirectional"))
      (node (ref "U1") (pin "3") (pinfunction "+IN_3") (pintype "input"))
    )
    (net (code "6") (name "A2") (class "Default")
      (node (ref "D22") (pin "1") (pinfunction "C_1") (pintype "passive"))
      (node (ref "P1") (pin "A4") (pinfunction "A4_A4") (pintype "bidirectional"))
      (node (ref "U1") (pin "5") (pinfunction "+IN_5") (pintype "input"))
    )
    (net (code "7") (name "A3") (class "Default")
      (node (ref "D23") (pin "1") (pinfunction "C_1") (pintype "passive"))
      (node (ref "P1") (pin "B3") (pinfunction "B3_B3") (pintype "bidirectional"))
      (node (ref "R23") (pin "2") (pinfunction "2_2") (pintype "passive"))
      (node (ref "U2") (pin "3") (pinfunction "+IN_3") (pintype "input"))
    )
    (net (code "8") (name "A4") (class "Default")
      (node (ref "D24") (pin "1") (pinfunction "C_1") (pintype "passive"))
      (node (ref "P1") (pin "B4") (pinfunction "B4_B4") (pintype "bidirectional"))
      (node (ref "R24") (pin "2") (pinfunction "2_2") (pintype "passive"))
      (node (ref "U2") (pin "5") (pinfunction "+IN_5") (pintype "input"))
    )
    (net (code "9") (name "A5") (class "Default")
      (node (ref "D25") (pin "1") (pinfunction "C_1") (pintype "passive"))
      (node (ref "P1") (pin "C3") (pinfunction "C3_C3") (pintype "bidirectional"))
      (node (ref "R25") (pin "2") (pinfunction "2_2") (pintype "passive"))
      (node (ref "U3") (pin "3") (pinfunction "+IN_3") (pintype "input"))
    )
    (net (code "10") (name "A6") (class "Default")
      (node (ref "D26") (pin "1") (pinfunction "C_1") (pintype "passive"))
      (node (ref "P1") (pin "D3") (pinfunction "D3_D3") (pintype "bidirectional"))
      (node (ref "R26") (pin "2") (pinfunction "2_2") (pintype "passive"))
      (node (ref "U3") (pin "5") (pinfunction "+IN_5") (pintype "input"))
    )
    (net (code "11") (name "A7") (class "Default")
      (node (ref "D27") (pin "1") (pinfunction "C_1") (pintype "passive"))
      (node (ref "P1") (pin "C4") (pinfunction "C4_C4") (pintype "bidirectional"))
      (node (ref "R27") (pin "2") (pinfunction "2_2") (pintype "passive"))
      (node (ref "U4") (pin "3") (pinfunction "+IN_3") (pintype "input"))
    )
    (net (code "12") (name "A8") (class "Default")
      (node (ref "D28") (pin "1") (pinfunction "C_1") (pintype "passive"))
      (node (ref "P1") (pin "D4") (pinfunction "D4_D4") (pintype "bidirectional"))
      (node (ref "R28") (pin "2") (pinfunction "2_2") (pintype "passive"))
      (node (ref "U4") (pin "5") (pinfunction "+IN_5") (pintype "input"))
    )
    (net (code "13") (name "A9") (class "Default")
      (node (ref "D29") (pin "1") (pinfunction "C_1") (pintype "passive"))
      (node (ref "P1") (pin "E3") (pinfunction "E3_E3") (pintype "bidirectional"))
      (node (ref "R29") (pin "2") (pinfunction "2_2") (pintype "passive"))
      (node (ref "U5") (pin "3") (pinfunction "+IN_3") (pintype "input"))
    )
    (net (code "14") (name "A10") (class "Default")
      (node (ref "D30") (pin "1") (pinfunction "C_1") (pintype "passive"))
      (node (ref "P1") (pin "F3") (pinfunction "F3_F3") (pintype "bidirectional"))
      (node (ref "R30") (pin "2") (pinfunction "2_2") (pintype "passive"))
      (node (ref "U5") (pin "5") (pinfunction "+IN_5") (pintype "input"))
    )
    (net (code "15") (name "BOOT0") (class "Default")
      (node (ref "P1") (pin "H4") (pinfunction "H4_H4") (pintype "bidirectional"))
      (node (ref "R36") (pin "1") (pinfunction "1_1") (pintype "passive"))
    )
    (net (code "16") (name "CANH") (class "Default")
      (node (ref "P1") (pin "J3") (pinfunction "J3_J3") (pintype "bidirectional"))
      (node (ref "R70") (pin "1") (pinfunction "1_1") (pintype "passive"))
      (node (ref "U7") (pin "7") (pinfunction "CANH_7") (pintype "bidirectional"))
    )
    (net (code "17") (name "CANL") (class "Default")
      (node (ref "P1") (pin "K3") (pinfunction "K3_K3") (pintype "bidirectional"))
      (node (ref "R70") (pin "2") (pinfunction "2_2") (pintype "passive"))
      (node (ref "U7") (pin "6") (pinfunction "CANL_6") (pintype "bidirectional"))
    )
    (net (code "18") (name "GND") (class "Default")
      (node (ref "C1") (pin "2") (pinfunction "2_2") (pintype "passive"))
      (node (ref "C10") (pin "2") (pinfunction "2_2") (pintype "passive"))
      (node (ref "C11") (pin "2") (pinfunction "2_2") (pintype "passive"))
      (node (ref "C12") (pin "2") (pinfunction "2_2") (pintype "passive"))
      (node (ref "C13") (pin "2") (pinfunction "2_2") (pintype "passive"))
      (node (ref "C14") (pin "2") (pinfunction "2_2") (pintype "passive"))
      (node (ref "C15") (pin "2") (pinfunction "2_2") (pintype "passive"))
      (node (ref "C2") (pin "2") (pinfunction "2_2") (pintype "passive"))
      (node (ref "C3") (pin "2") (pinfunction "2_2") (pintype "passive"))
      (node (ref "C4") (pin "2") (pinfunction "2_2") (pintype "passive"))
      (node (ref "C41") (pin "-") (pinfunction "-_-") (pintype "passive"))
      (node (ref "C42") (pin "2") (pinfunction "2_2") (pintype "passive"))
      (node (ref "C43") (pin "-") (pinfunction "-_-") (pintype "passive"))
      (node (ref "C44") (pin "2") (pinfunction "2_2") (pintype "passive"))
      (node (ref "C5") (pin "2") (pinfunction "2_2") (pintype "passive"))
      (node (ref "C7") (pin "2") (pinfunction "2_2") (pintype "passive"))
      (node (ref "C8") (pin "2") (pinfunction "2_2") (pintype "passive"))
      (node (ref "CR1") (pin "2") (pinfunction "2_2") (pintype "passive"))
      (node (ref "D1") (pin "2") (pinfunction "A_2") (pintype "passive"))
      (node (ref "D10") (pin "2") (pinfunction "A_2") (pintype "passive"))
      (node (ref "D11") (pin "2") (pinfunction "A_2") (pintype "passive"))
      (node (ref "D12") (pin "2") (pinfunction "A_2") (pintype "passive"))
      (node (ref "D2") (pin "2") (pinfunction "A_2") (pintype "passive"))
      (node (ref "D21") (pin "2") (pinfunction "A_2") (pintype "passive"))
      (node (ref "D22") (pin "2") (pinfunction "A_2") (pintype "passive"))
      (node (ref "D23") (pin "2") (pinfunction "A_2") (pintype "passive"))
      (node (ref "D24") (pin "2") (pinfunction "A_2") (pintype "passive"))
      (node (ref "D25") (pin "2") (pinfunction "A_2") (pintype "passive"))
      (node (ref "D26") (pin "2") (pinfunction "A_2") (pintype "passive"))
      (node (ref "D27") (pin "2") (pinfunction "A_2") (pintype "passive"))
      (node (ref "D28") (pin "2") (pinfunction "A_2") (pintype "passive"))
      (node (ref "D29") (pin "2") (pinfunction "A_2") (pintype "passive"))
      (node (ref "D3") (pin "2") (pinfunction "A_2") (pintype "passive"))
      (node (ref "D30") (pin "2") (pinfunction "A_2") (pintype "passive"))
      (node (ref "D33") (pin "2") (pinfunction "A_2") (pintype "passive"))
      (node (ref "D34") (pin "2") (pinfunction "A_2") (pintype "passive"))
      (node (ref "D35") (pin "2") (pinfunction "A_2") (pintype "passive"))
      (node (ref "D36") (pin "2") (pinfunction "A_2") (pintype "passive"))
      (node (ref "D4") (pin "2") (pinfunction "A_2") (pintype "passive"))
      (node (ref "D42") (pin "A") (pinfunction "C_A") (pintype "passive"))
      (node (ref "D5") (pin "2") (pinfunction "A_2") (pintype "passive"))
      (node (ref "D6") (pin "2") (pinfunction "A_2") (pintype "passive"))
      (node (ref "D7") (pin "2") (pinfunction "A_2") (pintype "passive"))
      (node (ref "D8") (pin "2") (pinfunction "A_2") (pintype "passive"))
      (node (ref "D9") (pin "2") (pinfunction "A_2") (pintype "passive"))
      (node (ref "IC1") (pin "3") (pinfunction "GND_3") (pintype "power_in"))
      (node (ref "IC1") (pin "5") (pinfunction "OFF_5") (pintype "input"))
      (node (ref "P1") (pin "L4") (pinfunction "L4_L4") (pintype "bidirectional"))
      (node (ref "P1") (pin "M4") (pinfunction "M4_M4") (pintype "bidirectional"))
      (node (ref "POWER") (pin "3") (pinfunction "3_3") (pintype "passive"))
      (node (ref "POWER") (pin "4") (pinfunction "4_4") (pintype "passive"))
      (node (ref "Q1") (pin "S") (pinfunction "S_S") (pintype "passive"))
      (node (ref "Q10") (pin "S") (pinfunction "S_S") (pintype "passive"))
      (node (ref "Q11") (pin "S") (pinfunction "S_S") (pintype "passive"))
      (node (ref "Q12") (pin "S") (pinfunction "S_S") (pintype "passive"))
      (node (ref "Q2") (pin "S") (pinfunction "S_S") (pintype "passive"))
      (node (ref "Q21") (pin "1") (pinfunction "S_1") (pintype "passive"))
      (node (ref "Q21") (pin "4") (pinfunction "S_4") (pintype "passive"))
      (node (ref "Q23") (pin "1") (pinfunction "S_1") (pintype "passive"))
      (node (ref "Q23") (pin "4") (pinfunction "S_4") (pintype "passive"))
      (node (ref "Q25") (pin "1") (pinfunction "S_1") (pintype "passive"))
      (node (ref "Q25") (pin "4") (pinfunction "S_4") (pintype "passive"))
      (node (ref "Q27") (pin "1") (pinfunction "S_1") (pintype "passive"))
      (node (ref "Q27") (pin "4") (pinfunction "S_4") (pintype "passive"))
      (node (ref "Q29") (pin "1") (pinfunction "S_1") (pintype "passive"))
      (node (ref "Q29") (pin "4") (pinfunction "S_4") (pintype "passive"))
      (node (ref "Q3") (pin "S") (pinfunction "S_S") (pintype "passive"))
      (node (ref "Q31") (pin "1") (pinfunction "S_1") (pintype "passive"))
      (node (ref "Q31") (pin "4") (pinfunction "S_4") (pintype "passive"))
      (node (ref "Q4") (pin "S") (pinfunction "S_S") (pintype "passive"))
      (node (ref "Q5") (pin "S") (pinfunction "S_S") (pintype "passive"))
      (node (ref "Q6") (pin "S") (pinfunction "S_S") (pintype "passive"))
      (node (ref "Q7") (pin "S") (pinfunction "S_S") (pintype "passive"))
      (node (ref "Q8") (pin "S") (pinfunction "S_S") (pintype "passive"))
      (node (ref "Q9") (pin "S") (pinfunction "S_S") (pintype "passive"))
      (node (ref "R1") (pin "2") (pinfunction "2_2") (pintype "passive"))
      (node (ref "R10") (pin "2") (pinfunction "2_2") (pintype "passive"))
      (node (ref "R11") (pin "2") (pinfunction "2_2") (pintype "passive"))
      (node (ref "R12") (pin "2") (pinfunction "2_2") (pintype "passive"))
      (node (ref "R2") (pin "2") (pinfunction "2_2") (pintype "passive"))
      (node (ref "R3") (pin "2") (pinfunction "2_2") (pintype "passive"))
      (node (ref "R4") (pin "2") (pinfunction "2_2") (pintype "passive"))
      (node (ref "R5") (pin "2") (pinfunction "2_2") (pintype "passive"))
      (node (ref "R6") (pin "2") (pinfunction "2_2") (pintype "passive"))
      (node (ref "R7") (pin "2") (pinfunction "2_2") (pintype "passive"))
      (node (ref "R8") (pin "2") (pinfunction "2_2") (pintype "passive"))
      (node (ref "R9") (pin "2") (pinfunction "2_2") (pintype "passive"))
      (node (ref "U1") (pin "4") (pinfunction "V-_4") (pintype "power_in"))
      (node (ref "U2") (pin "4") (pinfunction "V-_4") (pintype "power_in"))
      (node (ref "U3") (pin "4") (pinfunction "V-_4") (pintype "power_in"))
      (node (ref "U4") (pin "4") (pinfunction "V-_4") (pintype "power_in"))
      (node (ref "U5") (pin "4") (pinfunction "V-_4") (pintype "power_in"))
      (node (ref "U7") (pin "2") (pinfunction "GND_2") (pintype "bidirectional"))
      (node (ref "U7") (pin "8") (pinfunction "STBY_8") (pintype "bidirectional"))
    )
    (net (code "19") (name "I1") (class "Default")
      (node (ref "P1") (pin "G4") (pinfunction "G4_G4") (pintype "bidirectional"))
      (node (ref "R33") (pin "1") (pinfunction "1_1") (pintype "passive"))
    )
    (net (code "20") (name "I2") (class "Default")
      (node (ref "P1") (pin "F4") (pinfunction "F4_F4") (pintype "bidirectional"))
      (node (ref "R34") (pin "1") (pinfunction "1_1") (pintype "passive"))
    )
    (net (code "21") (name "I3") (class "Default")
      (node (ref "P1") (pin "E4") (pinfunction "E4_E4") (pintype "bidirectional"))
      (node (ref "R35") (pin "1") (pinfunction "1_1") (pintype "passive"))
    )
    (net (code "22") (name "Net-(D42-A)") (class "Default")
      (node (ref "D42") (pin "C") (pinfunction "A_C") (pintype "passive"))
      (node (ref "IC1") (pin "2") (pinfunction "OUT_2") (pintype "output"))
      (node (ref "L1") (pin "1") (pinfunction "1_1") (pintype "passive"))
    )
    (net (code "23") (name "OD1") (class "Default")
      (node (ref "D1") (pin "1") (pinfunction "C_1") (pintype "passive"))
      (node (ref "OPENDRAIN") (pin "2") (pinfunction "2_2") (pintype "passive"))
      (node (ref "P1") (pin "A1") (pinfunction "A1_A1") (pintype "bidirectional"))
      (node (ref "Q1") (pin "D") (pinfunction "D_D") (pintype "passive"))
    )
    (net (code "24") (name "OD2") (class "Default")
      (node (ref "D2") (pin "1") (pinfunction "C_1") (pintype "passive"))
      (node (ref "OPENDRAIN") (pin "4") (pinfunction "4_4") (pintype "passive"))
      (node (ref "P1") (pin "B1") (pinfunction "B1_B1") (pintype "bidirectional"))
      (node (ref "Q2") (pin "D") (pinfunction "D_D") (pintype "passive"))
    )
    (net (code "25") (name "OD3") (class "Default")
      (node (ref "D3") (pin "1") (pinfunction "C_1") (pintype "passive"))
      (node (ref "OPENDRAIN") (pin "6") (pinfunction "6_6") (pintype "passive"))
      (node (ref "P1") (pin "C1") (pinfunction "C1_C1") (pintype "bidirectional"))
      (node (ref "Q3") (pin "D") (pinfunction "D_D") (pintype "passive"))
    )
    (net (code "26") (name "OD4") (class "Default")
      (node (ref "D4") (pin "1") (pinfunction "C_1") (pintype "passive"))
      (node (ref "OPENDRAIN") (pin "8") (pinfunction "8_8") (pintype "passive"))
      (node (ref "P1") (pin "D1") (pinfunction "D1_D1") (pintype "bidirectional"))
      (node (ref "Q4") (pin "D") (pinfunction "D_D") (pintype "passive"))
    )
    (net (code "27") (name "OD5") (class "Default")
      (node (ref "D5") (pin "1") (pinfunction "C_1") (pintype "passive"))
      (node (ref "OPENDRAIN") (pin "10") (pinfunction "10_10") (pintype "passive"))
      (node (ref "P1") (pin "E1") (pinfunction "E1_E1") (pintype "bidirectional"))
      (node (ref "Q5") (pin "D") (pinfunction "D_D") (pintype "passive"))
    )
    (net (code "28") (name "OD6") (class "Default")
      (node (ref "D6") (pin "1") (pinfunction "C_1") (pintype "passive"))
      (node (ref "OPENDRAIN") (pin "12") (pinfunction "12_12") (pintype "passive"))
      (node (ref "P1") (pin "F1") (pinfunction "F1_F1") (pintype "bidirectional"))
      (node (ref "Q6") (pin "D") (pinfunction "D_D") (pintype "passive"))
    )
    (net (code "29") (name "OD7") (class "Default")
      (node (ref "D7") (pin "1") (pinfunction "C_1") (pintype "passive"))
      (node (ref "OPENDRAIN") (pin "14") (pinfunction "14_14") (pintype "passive"))
      (node (ref "P1") (pin "G1") (pinfunction "G1_G1") (pintype "bidirectional"))
      (node (ref "Q7") (pin "D") (pinfunction "D_D") (pintype "passive"))
    )
    (net (code "30") (name "OD8") (class "Default")
      (node (ref "D8") (pin "1") (pinfunction "C_1") (pintype "passive"))
      (node (ref "OPENDRAIN") (pin "16") (pinfunction "16_16") (pintype "passive"))
      (node (ref "P1") (pin "H1") (pinfunction "H1_H1") (pintype "bidirectional"))
      (node (ref "Q8") (pin "D") (pinfunction "D_D") (pintype "passive"))
    )
    (net (code "31") (name "OD9") (class "Default")
      (node (ref "D9") (pin "1") (pinfunction "C_1") (pintype "passive"))
      (node (ref "OPENDRAIN") (pin "18") (pinfunction "18_18") (pintype "passive"))
      (node (ref "P1") (pin "J1") (pinfunction "J1_J1") (pintype "bidirectional"))
      (node (ref "Q9") (pin "D") (pinfunction "D_D") (pintype "passive"))
    )
    (net (code "32") (name "OD10") (class "Default")
      (node (ref "D10") (pin "1") (pinfunction "C_1") (pintype "passive"))
      (node (ref "OPENDRAIN") (pin "20") (pinfunction "20_20") (pintype "passive"))
      (node (ref "P1") (pin "K1") (pinfunction "K1_K1") (pintype "bidirectional"))
      (node (ref "Q10") (pin "D") (pinfunction "D_D") (pintype "passive"))
    )
    (net (code "33") (name "OD11") (class "Default")
      (node (ref "D12") (pin "1") (pinfunction "C_1") (pintype "passive"))
      (node (ref "OPENDRAIN") (pin "22") (pinfunction "22_22") (pintype "passive"))
      (node (ref "P1") (pin "L1") (pinfunction "L1_L1") (pintype "bidirectional"))
      (node (ref "Q11") (pin "D") (pinfunction "D_D") (pintype "passive"))
    )
    (net (code "34") (name "OD12") (class "Default")
      (node (ref "D11") (pin "1") (pinfunction "C_1") (pintype "passive"))
      (node (ref "OPENDRAIN") (pin "24") (pinfunction "24_24") (pintype "passive"))
      (node (ref "P1") (pin "M1") (pinfunction "M1_M1") (pintype "bidirectional"))
      (node (ref "Q12") (pin "D") (pinfunction "D_D") (pintype "passive"))
    )
    (net (code "35") (name "PP1") (class "Default")
      (node (ref "P1") (pin "A2") (pinfunction "A2_A2") (pintype "bidirectional"))
      (node (ref "Q21") (pin "3") (pinfunction "D_3") (pintype "passive"))
      (node (ref "Q22") (pin "3") (pinfunction "D_3") (pintype "passive"))
    )
    (net (code "36") (name "PP2") (class "Default")
      (node (ref "P1") (pin "B2") (pinfunction "B2_B2") (pintype "bidirectional"))
      (node (ref "Q21") (pin "6") (pinfunction "D_6") (pintype "passive"))
      (node (ref "Q22") (pin "6") (pinfunction "D_6") (pintype "passive"))
    )
    (net (code "37") (name "PP3") (class "Default")
      (node (ref "P1") (pin "C2") (pinfunction "C2_C2") (pintype "bidirectional"))
      (node (ref "Q23") (pin "3") (pinfunction "D_3") (pintype "passive"))
      (node (ref "Q24") (pin "3") (pinfunction "D_3") (pintype "passive"))
    )
    (net (code "38") (name "PP4") (class "Default")
      (node (ref "P1") (pin "D2") (pinfunction "D2_D2") (pintype "bidirectional"))
      (node (ref "Q23") (pin "6") (pinfunction "D_6") (pintype "passive"))
      (node (ref "Q24") (pin "6") (pinfunction "D_6") (pintype "passive"))
    )
    (net (code "39") (name "PP5") (class "Default")
      (node (ref "P1") (pin "E2") (pinfunction "E2_E2") (pintype "bidirectional"))
      (node (ref "Q25") (pin "3") (pinfunction "D_3") (pintype "passive"))
      (node (ref "Q26") (pin "3") (pinfunction "D_3") (pintype "passive"))
    )
    (net (code "40") (name "PP6") (class "Default")
      (node (ref "P1") (pin "F2") (pinfunction "F2_F2") (pintype "bidirectional"))
      (node (ref "Q25") (pin "6") (pinfunction "D_6") (pintype "passive"))
      (node (ref "Q26") (pin "6") (pinfunction "D_6") (pintype "passive"))
    )
    (net (code "41") (name "PP7") (class "Default")
      (node (ref "P1") (pin "G2") (pinfunction "G2_G2") (pintype "bidirectional"))
      (node (ref "Q27") (pin "3") (pinfunction "D_3") (pintype "passive"))
      (node (ref "Q28") (pin "3") (pinfunction "D_3") (pintype "passive"))
    )
    (net (code "42") (name "PP8") (class "Default")
      (node (ref "P1") (pin "H2") (pinfunction "H2_H2") (pintype "bidirectional"))
      (node (ref "Q27") (pin "6") (pinfunction "D_6") (pintype "passive"))
      (node (ref "Q28") (pin "6") (pinfunction "D_6") (pintype "passive"))
    )
    (net (code "43") (name "PP9") (class "Default")
      (node (ref "P1") (pin "J2") (pinfunction "J2_J2") (pintype "bidirectional"))
      (node (ref "Q29") (pin "3") (pinfunction "D_3") (pintype "passive"))
      (node (ref "Q30") (pin "3") (pinfunction "D_3") (pintype "passive"))
    )
    (net (code "44") (name "PP10") (class "Default")
      (node (ref "P1") (pin "K2") (pinfunction "K2_K2") (pintype "bidirectional"))
      (node (ref "Q29") (pin "6") (pinfunction "D_6") (pintype "passive"))
      (node (ref "Q30") (pin "6") (pinfunction "D_6") (pintype "passive"))
    )
    (net (code "45") (name "PP11") (class "Default")
      (node (ref "P1") (pin "G3") (pinfunction "G3_G3") (pintype "bidirectional"))
      (node (ref "Q31") (pin "3") (pinfunction "D_3") (pintype "passive"))
      (node (ref "Q32") (pin "3") (pinfunction "D_3") (pintype "passive"))
    )
    (net (code "46") (name "PP12") (class "Default")
      (node (ref "P1") (pin "H3") (pinfunction "H3_H3") (pintype "bidirectional"))
      (node (ref "Q31") (pin "6") (pinfunction "D_6") (pintype "passive"))
      (node (ref "Q32") (pin "6") (pinfunction "D_6") (pintype "passive"))
    )
    (net (code "47") (name "USB-D+") (class "Default")
      (node (ref "CAN_DIGITAL_USB") (pin "8") (pinfunction "8_8") (pintype "passive"))
      (node (ref "P1") (pin "K4") (pinfunction "K4_K4") (pintype "bidirectional"))
    )
    (net (code "48") (name "USB-D-") (class "Default")
      (node (ref "CAN_DIGITAL_USB") (pin "9") (pinfunction "9_9") (pintype "passive"))
      (node (ref "P1") (pin "J4") (pinfunction "J4_J4") (pintype "bidirectional"))
    )
    (net (code "49") (name "µC_A1") (class "Default")
      (node (ref "ANALOGIN") (pin "3") (pinfunction "3_3") (pintype "passive"))
      (node (ref "U1") (pin "1") (pinfunction "OUT_1") (pintype "output"))
      (node (ref "U1") (pin "2") (pinfunction "-IN_2") (pintype "input"))
    )
    (net (code "50") (name "µC_A2") (class "Default")
      (node (ref "ANALOGIN") (pin "4") (pinfunction "4_4") (pintype "passive"))
      (node (ref "U1") (pin "6") (pinfunction "-IN_6") (pintype "input"))
      (node (ref "U1") (pin "7") (pinfunction "OUT_7") (pintype "output"))
    )
    (net (code "51") (name "µC_A3") (class "Default")
      (node (ref "ANALOGIN") (pin "5") (pinfunction "5_5") (pintype "passive"))
      (node (ref "U2") (pin "1") (pinfunction "OUT_1") (pintype "output"))
      (node (ref "U2") (pin "2") (pinfunction "-IN_2") (pintype "input"))
    )
    (net (code "52") (name "µC_A4") (class "Default")
      (node (ref "ANALOGIN") (pin "6") (pinfunction "6_6") (pintype "passive"))
      (node (ref "U2") (pin "6") (pinfunction "-IN_6") (pintype "input"))
      (node (ref "U2") (pin "7") (pinfunction "OUT_7") (pintype "output"))
    )
    (net (code "53") (name "µC_A5") (class "Default")
      (node (ref "ANALOGIN") (pin "1") (pinfunction "1_1") (pintype "passive"))
      (node (ref "U3") (pin "1") (pinfunction "OUT_1") (pintype "output"))
      (node (ref "U3") (pin "2") (pinfunction "-IN_2") (pintype "input"))
    )
    (net (code "54") (name "µC_A6") (class "Default")
      (node (ref "ANALOGIN") (pin "2") (pinfunction "2_2") (pintype "passive"))
      (node (ref "U3") (pin "6") (pinfunction "-IN_6") (pintype "input"))
      (node (ref "U3") (pin "7") (pinfunction "OUT_7") (pintype "output"))
    )
    (net (code "55") (name "µC_A7") (class "Default")
      (node (ref "ANALOGIN") (pin "10") (pinfunction "10_10") (pintype "passive"))
      (node (ref "U4") (pin "1") (pinfunction "OUT_1") (pintype "output"))
      (node (ref "U4") (pin "2") (pinfunction "-IN_2") (pintype "input"))
    )
    (net (code "56") (name "µC_A8") (class "Default")
      (node (ref "ANALOGIN") (pin "9") (pinfunction "9_9") (pintype "passive"))
      (node (ref "U4") (pin "6") (pinfunction "-IN_6") (pintype "input"))
      (node (ref "U4") (pin "7") (pinfunction "OUT_7") (pintype "output"))
    )
    (net (code "57") (name "µC_A9") (class "Default")
      (node (ref "ANALOGIN") (pin "8") (pinfunction "8_8") (pintype "passive"))
      (node (ref "U5") (pin "1") (pinfunction "OUT_1") (pintype "output"))
      (node (ref "U5") (pin "2") (pinfunction "-IN_2") (pintype "input"))
    )
    (net (code "58") (name "µC_A10") (class "Default")
      (node (ref "ANALOGIN") (pin "7") (pinfunction "7_7") (pintype "passive"))
      (node (ref "U5") (pin "6") (pinfunction "-IN_6") (pintype "input"))
      (node (ref "U5") (pin "7") (pinfunction "OUT_7") (pintype "output"))
    )
    (net (code "59") (name "µC_BOOT0") (class "Default")
      (node (ref "CAN_DIGITAL_USB") (pin "4") (pinfunction "4_4") (pintype "passive"))
      (node (ref "D36") (pin "1") (pinfunction "C_1") (pintype "passive"))
      (node (ref "R36") (pin "2") (pinfunction "2_2") (pintype "passive"))
    )
    (net (code "60") (name "µC_CAN_RX") (class "Default")
      (node (ref "CAN_DIGITAL_USB") (pin "3") (pinfunction "3_3") (pintype "passive"))
      (node (ref "U7") (pin "4") (pinfunction "RXD_4") (pintype "bidirectional"))
    )
    (net (code "61") (name "µC_CAN_TX") (class "Default")
      (node (ref "CAN_DIGITAL_USB") (pin "2") (pinfunction "2_2") (pintype "passive"))
      (node (ref "U7") (pin "1") (pinfunction "TXD_1") (pintype "bidirectional"))
    )
    (net (code "62") (name "µC_I1") (class "Default")
      (node (ref "CAN_DIGITAL_USB") (pin "6") (pinfunction "6_6") (pintype "passive"))
      (node (ref "D33") (pin "1") (pinfunction "C_1") (pintype "passive"))
      (node (ref "R33") (pin "2") (pinfunction "2_2") (pintype "passive"))
    )
    (net (code "63") (name "µC_I2") (class "Default")
      (node (ref "CAN_DIGITAL_USB") (pin "7") (pinfunction "7_7") (pintype "passive"))
      (node (ref "D34") (pin "1") (pinfunction "C_1") (pintype "passive"))
      (node (ref "R34") (pin "2") (pinfunction "2_2") (pintype "passive"))
    )
    (net (code "64") (name "µC_I3") (class "Default")
      (node (ref "CAN_DIGITAL_USB") (pin "5") (pinfunction "5_5") (pintype "passive"))
      (node (ref "D35") (pin "1") (pinfunction "C_1") (pintype "passive"))
      (node (ref "R35") (pin "2") (pinfunction "2_2") (pintype "passive"))
    )
    (net (code "65") (name "µC_OD1") (class "Default")
      (node (ref "OPENDRAIN") (pin "1") (pinfunction "1_1") (pintype "passive"))
      (node (ref "Q1") (pin "G") (pinfunction "G_G") (pintype "passive"))
      (node (ref "R1") (pin "1") (pinfunction "1_1") (pintype "passive"))
    )
    (net (code "66") (name "µC_OD2") (class "Default")
      (node (ref "OPENDRAIN") (pin "3") (pinfunction "3_3") (pintype "passive"))
      (node (ref "Q2") (pin "G") (pinfunction "G_G") (pintype "passive"))
      (node (ref "R2") (pin "1") (pinfunction "1_1") (pintype "passive"))
    )
    (net (code "67") (name "µC_OD3") (class "Default")
      (node (ref "OPENDRAIN") (pin "5") (pinfunction "5_5") (pintype "passive"))
      (node (ref "Q3") (pin "G") (pinfunction "G_G") (pintype "passive"))
      (node (ref "R3") (pin "1") (pinfunction "1_1") (pintype "passive"))
    )
    (net (code "68") (name "µC_OD4") (class "Default")
      (node (ref "OPENDRAIN") (pin "7") (pinfunction "7_7") (pintype "passive"))
      (node (ref "Q4") (pin "G") (pinfunction "G_G") (pintype "passive"))
      (node (ref "R4") (pin "1") (pinfunction "1_1") (pintype "passive"))
    )
    (net (code "69") (name "µC_OD5") (class "Default")
      (node (ref "OPENDRAIN") (pin "9") (pinfunction "9_9") (pintype "passive"))
      (node (ref "Q5") (pin "G") (pinfunction "G_G") (pintype "passive"))
      (node (ref "R5") (pin "1") (pinfunction "1_1") (pintype "passive"))
    )
    (net (code "70") (name "µC_OD6") (class "Default")
      (node (ref "OPENDRAIN") (pin "11") (pinfunction "11_11") (pintype "passive"))
      (node (ref "Q6") (pin "G") (pinfunction "G_G") (pintype "passive"))
      (node (ref "R6") (pin "1") (pinfunction "1_1") (pintype "passive"))
    )
    (net (code "71") (name "µC_OD7") (class "Default")
      (node (ref "OPENDRAIN") (pin "13") (pinfunction "13_13") (pintype "passive"))
      (node (ref "Q7") (pin "G") (pinfunction "G_G") (pintype "passive"))
      (node (ref "R7") (pin "1") (pinfunction "1_1") (pintype "passive"))
    )
    (net (code "72") (name "µC_OD8") (class "Default")
      (node (ref "OPENDRAIN") (pin "15") (pinfunction "15_15") (pintype "passive"))
      (node (ref "Q8") (pin "G") (pinfunction "G_G") (pintype "passive"))
      (node (ref "R8") (pin "1") (pinfunction "1_1") (pintype "passive"))
    )
    (net (code "73") (name "µC_OD9") (class "Default")
      (node (ref "OPENDRAIN") (pin "17") (pinfunction "17_17") (pintype "passive"))
      (node (ref "Q9") (pin "G") (pinfunction "G_G") (pintype "passive"))
      (node (ref "R9") (pin "1") (pinfunction "1_1") (pintype "passive"))
    )
    (net (code "74") (name "µC_OD10") (class "Default")
      (node (ref "OPENDRAIN") (pin "19") (pinfunction "19_19") (pintype "passive"))
      (node (ref "Q10") (pin "G") (pinfunction "G_G") (pintype "passive"))
      (node (ref "R10") (pin "1") (pinfunction "1_1") (pintype "passive"))
    )
    (net (code "75") (name "µC_OD11") (class "Default")
      (node (ref "OPENDRAIN") (pin "21") (pinfunction "21_21") (pintype "passive"))
      (node (ref "Q11") (pin "G") (pinfunction "G_G") (pintype "passive"))
      (node (ref "R11") (pin "1") (pinfunction "1_1") (pintype "passive"))
    )
    (net (code "76") (name "µC_OD12") (class "Default")
      (node (ref "OPENDRAIN") (pin "23") (pinfunction "23_23") (pintype "passive"))
      (node (ref "Q12") (pin "G") (pinfunction "G_G") (pintype "passive"))
      (node (ref "R12") (pin "1") (pinfunction "1_1") (pintype "passive"))
    )
    (net (code "77") (name "µC_PP1") (class "Default")
      (node (ref "PUSHPULL") (pin "2") (pinfunction "2_2") (pintype "passive"))
      (node (ref "Q21") (pin "5") (pinfunction "G_5") (pintype "passive"))
      (node (ref "Q22") (pin "5") (pinfunction "G_5") (pintype "passive"))
    )
    (net (code "78") (name "µC_PP2") (class "Default")
      (node (ref "PUSHPULL") (pin "1") (pinfunction "1_1") (pintype "passive"))
      (node (ref "Q21") (pin "2") (pinfunction "G_2") (pintype "passive"))
      (node (ref "Q22") (pin "2") (pinfunction "G_2") (pintype "passive"))
    )
    (net (code "79") (name "µC_PP3") (class "Default")
      (node (ref "PUSHPULL") (pin "4") (pinfunction "4_4") (pintype "passive"))
      (node (ref "Q23") (pin "5") (pinfunction "G_5") (pintype "passive"))
      (node (ref "Q24") (pin "5") (pinfunction "G_5") (pintype "passive"))
    )
    (net (code "80") (name "µC_PP4") (class "Default")
      (node (ref "PUSHPULL") (pin "3") (pinfunction "3_3") (pintype "passive"))
      (node (ref "Q23") (pin "2") (pinfunction "G_2") (pintype "passive"))
      (node (ref "Q24") (pin "2") (pinfunction "G_2") (pintype "passive"))
    )
    (net (code "81") (name "µC_PP5") (class "Default")
      (node (ref "PUSHPULL") (pin "6") (pinfunction "6_6") (pintype "passive"))
      (node (ref "Q25") (pin "5") (pinfunction "G_5") (pintype "passive"))
      (node (ref "Q26") (pin "5") (pinfunction "G_5") (pintype "passive"))
    )
    (net (code "82") (name "µC_PP6") (class "Default")
      (node (ref "PUSHPULL") (pin "5") (pinfunction "5_5") (pintype "passive"))
      (node (ref "Q25") (pin "2") (pinfunction "G_2") (pintype "passive"))
      (node (ref "Q26") (pin "2") (pinfunction "G_2") (pintype "passive"))
    )
    (net (code "83") (name "µC_PP7") (class "Default")
      (node (ref "PUSHPULL") (pin "8") (pinfunction "8_8") (pintype "passive"))
      (node (ref "Q27") (pin "5") (pinfunction "G_5") (pintype "passive"))
      (node (ref "Q28") (pin "5") (pinfunction "G_5") (pintype "passive"))
    )
    (net (code "84") (name "µC_PP8") (class "Default")
      (node (ref "PUSHPULL") (pin "7") (pinfunction "7_7") (pintype "passive"))
      (node (ref "Q27") (pin "2") (pinfunction "G_2") (pintype "passive"))
      (node (ref "Q28") (pin "2") (pinfunction "G_2") (pintype "passive"))
    )
    (net (code "85") (name "µC_PP9") (class "Default")
      (node (ref "PUSHPULL") (pin "10") (pinfunction "10_10") (pintype "passive"))
      (node (ref "Q29") (pin "5") (pinfunction "G_5") (pintype "passive"))
      (node (ref "Q30") (pin "5") (pinfunction "G_5") (pintype "passive"))
    )
    (net (code "86") (name "µC_PP10") (class "Default")
      (node (ref "PUSHPULL") (pin "9") (pinfunction "9_9") (pintype "passive"))
      (node (ref "Q29") (pin "2") (pinfunction "G_2") (pintype "passive"))
      (node (ref "Q30") (pin "2") (pinfunction "G_2") (pintype "passive"))
    )
    (net (code "87") (name "µC_PP11") (class "Default")
      (node (ref "PUSHPULL") (pin "11") (pinfunction "11_11") (pintype "passive"))
      (node (ref "Q31") (pin "5") (pinfunction "G_5") (pintype "passive"))
      (node (ref "Q32") (pin "5") (pinfunction "G_5") (pintype "passive"))
    )
    (net (code "88") (name "µC_PP12") (class "Default")
      (node (ref "PUSHPULL") (pin "12") (pinfunction "12_12") (pintype "passive"))
      (node (ref "Q31") (pin "2") (pinfunction "G_2") (pintype "passive"))
      (node (ref "Q32") (pin "2") (pinfunction "G_2") (pintype "passive"))
    )
  )
)
